# Supply_Wenzel.net
KiCad netlist of a schematic drawn in Altium Designer
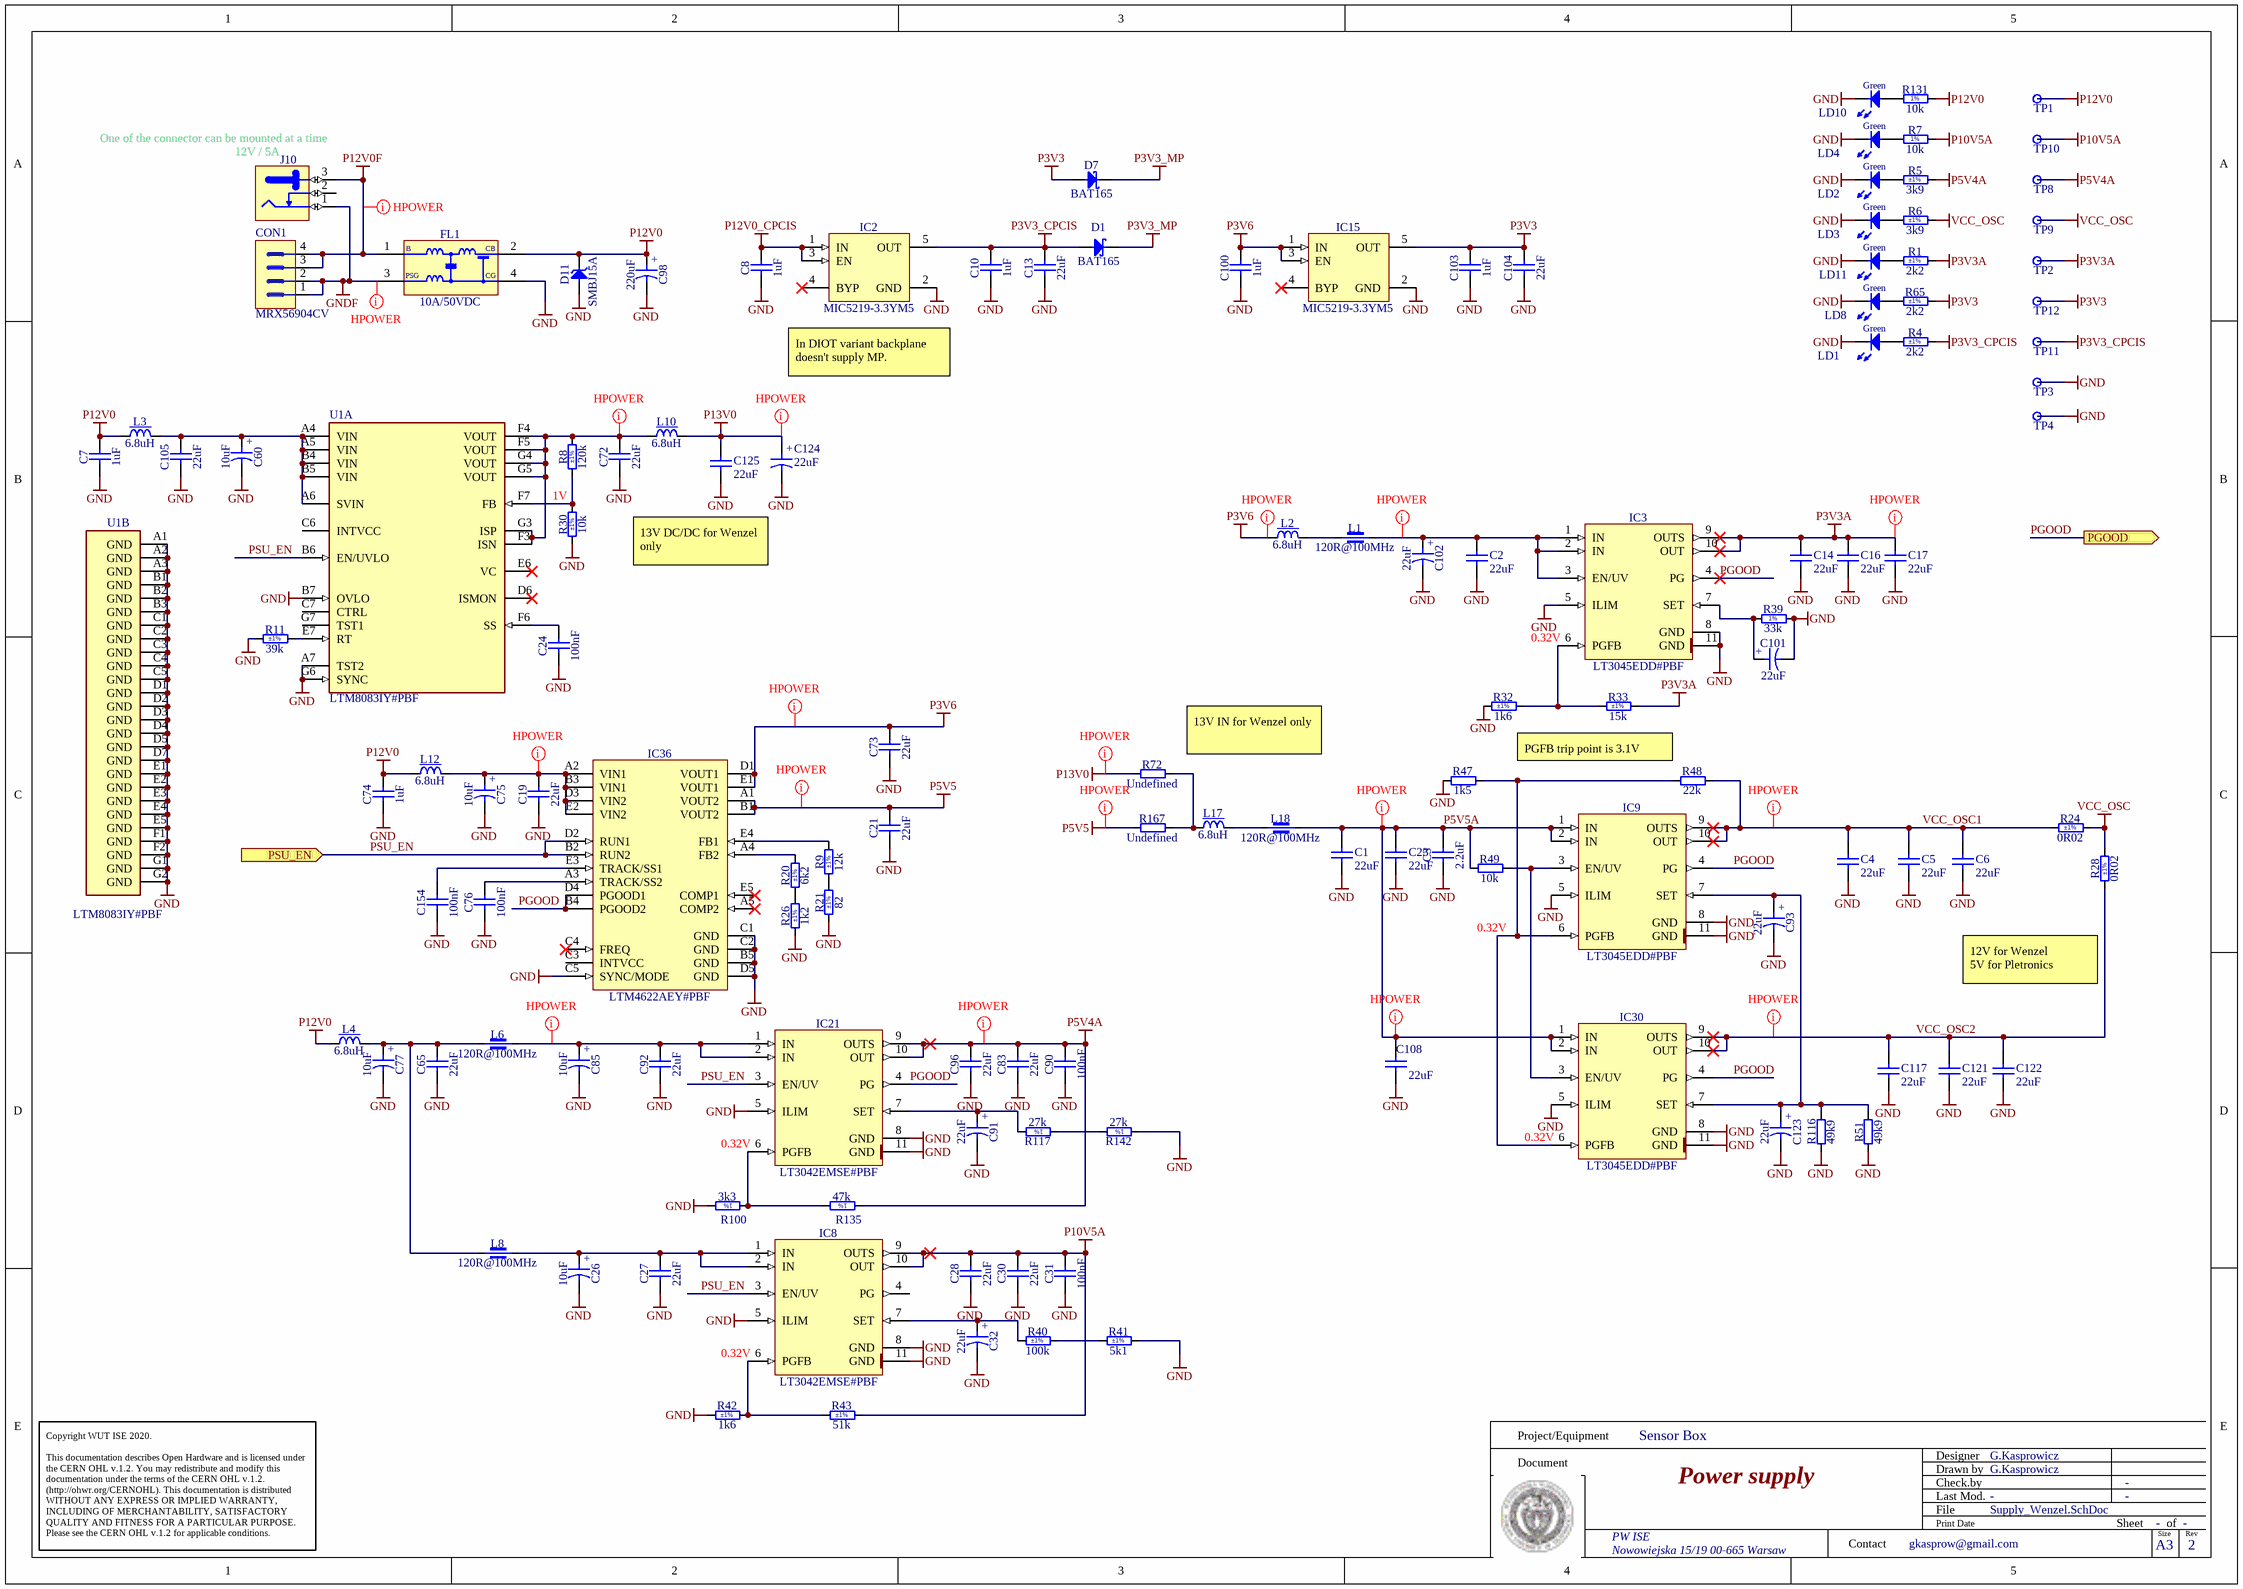
[diagram p0: Supply_Wenzel.SchDoc]

(export (version "E")
  (design (tool "Eeschema 10.0.6"))
  (components
    (comp (ref "C1")
      (value "22uF")
      (footprint "CAPC2012X135N")
      (description "Non-polarised capacitor")
      (fields
        (field (name "PART NUMBER") "CC0805_22UF_16V_10%_X5R")
        (field (name "VOLTAGE") "16V")
        (field (name "AUTHOR") "CERN DEM JLC")
      )
      (libsource (lib "Capacitors") (part "Capacitor - non polarized"))
    )
    (comp (ref "C2")
      (value "22uF")
      (footprint "CAPC2012X135N")
      (description "Non-polarised capacitor")
      (fields
        (field (name "PART NUMBER") "CC0805_22UF_16V_10%_X5R")
        (field (name "VOLTAGE") "16V")
        (field (name "AUTHOR") "CERN DEM JLC")
      )
      (libsource (lib "Capacitors") (part "Capacitor - non polarized"))
    )
    (comp (ref "C3")
      (value "2.2uF")
      (footprint "CAPC1608X87N")
      (description "Non-polarised capacitor")
      (fields
        (field (name "PART NUMBER") "CC0603_2.2UF_16V_10%_X5R")
        (field (name "VOLTAGE") "16V")
        (field (name "AUTHOR") "CERN DEM JLC")
      )
      (libsource (lib "Capacitors") (part "Capacitor - non polarized"))
    )
    (comp (ref "C4")
      (value "22uF")
      (footprint "CAPC2012X135N")
      (description "Non-polarised capacitor")
      (fields
        (field (name "PART NUMBER") "CC0805_22UF_16V_10%_X5R")
        (field (name "VOLTAGE") "16V")
        (field (name "AUTHOR") "CERN DEM JLC")
      )
      (libsource (lib "Capacitors") (part "Capacitor - non polarized"))
    )
    (comp (ref "C5")
      (value "22uF")
      (footprint "CAPC2012X135N")
      (description "Non-polarised capacitor")
      (fields
        (field (name "PART NUMBER") "CC0805_22UF_16V_10%_X5R")
        (field (name "VOLTAGE") "16V")
        (field (name "AUTHOR") "CERN DEM JLC")
      )
      (libsource (lib "Capacitors") (part "Capacitor - non polarized"))
    )
    (comp (ref "C6")
      (value "22uF")
      (footprint "CAPC2012X135N")
      (description "Non-polarised capacitor")
      (fields
        (field (name "PART NUMBER") "CC0805_22UF_16V_10%_X5R")
        (field (name "VOLTAGE") "16V")
        (field (name "AUTHOR") "CERN DEM JLC")
      )
      (libsource (lib "Capacitors") (part "Capacitor - non polarized"))
    )
    (comp (ref "C7")
      (value "1uF")
      (footprint "CAPC1608X87N")
      (description "Non-polarised capacitor")
      (fields
        (field (name "PART NUMBER") "CC0603_1UF_25V_10%_X7R")
        (field (name "VOLTAGE") "25V")
        (field (name "AUTHOR") "CERN DEM JLC")
      )
      (libsource (lib "Capacitors") (part "Capacitor - non polarized"))
    )
    (comp (ref "C8")
      (value "1uF")
      (footprint "CAPC1608X87N")
      (description "Non-polarised capacitor")
      (fields
        (field (name "PART NUMBER") "CC0603_1UF_25V_10%_X7R")
        (field (name "VOLTAGE") "25V")
        (field (name "AUTHOR") "CERN DEM JLC")
      )
      (libsource (lib "Capacitors") (part "Capacitor - non polarized"))
    )
    (comp (ref "C10")
      (value "1uF")
      (footprint "CAPC1608X87N")
      (description "Non-polarised capacitor")
      (fields
        (field (name "PART NUMBER") "CC0603_1UF_25V_10%_X7R")
        (field (name "VOLTAGE") "25V")
        (field (name "AUTHOR") "CERN DEM JLC")
      )
      (libsource (lib "Capacitors") (part "Capacitor - non polarized"))
    )
    (comp (ref "C13")
      (value "22uF")
      (footprint "CAPC1608X90N")
      (description "Non-polarised capacitor")
      (fields
        (field (name "PART NUMBER") "CC0603_22UF_6.3V_20%_X5R")
        (field (name "VOLTAGE") "6.3V")
        (field (name "AUTHOR") "CERN DEM JLC")
      )
      (libsource (lib "Capacitors") (part "Capacitor - non polarized"))
    )
    (comp (ref "C14")
      (value "22uF")
      (footprint "CAPC2012X135N")
      (description "Non-polarised capacitor")
      (fields
        (field (name "PART NUMBER") "CC0805_22UF_16V_10%_X5R")
        (field (name "VOLTAGE") "16V")
        (field (name "AUTHOR") "CERN DEM JLC")
      )
      (libsource (lib "Capacitors") (part "Capacitor - non polarized"))
    )
    (comp (ref "C16")
      (value "22uF")
      (footprint "CAPC2012X135N")
      (description "Non-polarised capacitor")
      (fields
        (field (name "PART NUMBER") "CC0805_22UF_16V_10%_X5R")
        (field (name "VOLTAGE") "16V")
        (field (name "AUTHOR") "CERN DEM JLC")
      )
      (libsource (lib "Capacitors") (part "Capacitor - non polarized"))
    )
    (comp (ref "C17")
      (value "22uF")
      (footprint "CAPC2012X135N")
      (description "Non-polarised capacitor")
      (fields
        (field (name "PART NUMBER") "CC0805_22UF_16V_10%_X5R")
        (field (name "VOLTAGE") "16V")
        (field (name "AUTHOR") "CERN DEM JLC")
      )
      (libsource (lib "Capacitors") (part "Capacitor - non polarized"))
    )
    (comp (ref "C19")
      (value "22uF")
      (footprint "CAPC2012X135N")
      (description "Non-polarised capacitor")
      (fields
        (field (name "PART NUMBER") "CC0805_22UF_16V_10%_X5R")
        (field (name "VOLTAGE") "16V")
        (field (name "AUTHOR") "CERN DEM JLC")
      )
      (libsource (lib "Capacitors") (part "Capacitor - non polarized"))
    )
    (comp (ref "C21")
      (value "22uF")
      (footprint "CAPC2012X135N")
      (description "Non-polarised capacitor")
      (fields
        (field (name "PART NUMBER") "CC0805_22UF_16V_10%_X5R")
        (field (name "VOLTAGE") "16V")
        (field (name "AUTHOR") "CERN DEM JLC")
      )
      (libsource (lib "Capacitors") (part "Capacitor - non polarized"))
    )
    (comp (ref "C23")
      (value "22uF")
      (footprint "CAPC2012X135N")
      (description "Non-polarised capacitor")
      (fields
        (field (name "PART NUMBER") "CC0805_22UF_16V_10%_X5R")
        (field (name "VOLTAGE") "16V")
        (field (name "AUTHOR") "CERN DEM JLC")
      )
      (libsource (lib "Capacitors") (part "Capacitor - non polarized"))
    )
    (comp (ref "C24")
      (value "100nF")
      (footprint "CAPC1005X55N")
      (description "Non-polarised capacitor")
      (fields
        (field (name "PART NUMBER") "CC0402_100NF_16V_10%_X7R")
        (field (name "VOLTAGE") "16V")
        (field (name "AUTHOR") "CERN DEM JLC")
      )
      (libsource (lib "Capacitors") (part "Capacitor - non polarized"))
    )
    (comp (ref "C26")
      (value "10uF")
      (footprint "CAPMP3216X180N")
      (description "Polarised capacitor")
      (fields
        (field (name "PART NUMBER") "CTE3216-18_10UF_16V_20%_AVX_TCJ")
        (field (name "VOLTAGE") "16V")
        (field (name "AUTHOR") "CERN DEM JLC")
      )
      (libsource (lib "Capacitors") (part "Capacitor - polarized"))
    )
    (comp (ref "C27")
      (value "22uF")
      (footprint "CAPC2012X135N")
      (description "Non-polarised capacitor")
      (fields
        (field (name "PART NUMBER") "CC0805_22UF_16V_10%_X5R")
        (field (name "VOLTAGE") "16V")
        (field (name "AUTHOR") "CERN DEM JLC")
      )
      (libsource (lib "Capacitors") (part "Capacitor - non polarized"))
    )
    (comp (ref "C28")
      (value "22uF")
      (footprint "CAPC2012X135N")
      (description "Non-polarised capacitor")
      (fields
        (field (name "PART NUMBER") "CC0805_22UF_16V_10%_X5R")
        (field (name "VOLTAGE") "16V")
        (field (name "AUTHOR") "CERN DEM JLC")
      )
      (libsource (lib "Capacitors") (part "Capacitor - non polarized"))
    )
    (comp (ref "C30")
      (value "22uF")
      (footprint "CAPC2012X135N")
      (description "Non-polarised capacitor")
      (fields
        (field (name "PART NUMBER") "CC0805_22UF_16V_10%_X5R")
        (field (name "VOLTAGE") "16V")
        (field (name "AUTHOR") "CERN DEM JLC")
      )
      (libsource (lib "Capacitors") (part "Capacitor - non polarized"))
    )
    (comp (ref "C31")
      (value "100nF")
      (footprint "CAPC1005X55N")
      (description "Non-polarised capacitor")
      (fields
        (field (name "PART NUMBER") "CC0402_100NF_16V_10%_X5R")
        (field (name "VOLTAGE") "16V")
        (field (name "AUTHOR") "CERN DEM JLC")
      )
      (libsource (lib "Capacitors") (part "Capacitor - non polarized"))
    )
    (comp (ref "C32")
      (value "22uF")
      (footprint "CAPMP3528X210N")
      (description "Polarised capacitor")
      (fields
        (field (name "PART NUMBER") "CTE3528-21_22UF_10V_10%_LESR0700")
        (field (name "VOLTAGE") "10V")
        (field (name "AUTHOR") "CERN DEM JLC")
      )
      (libsource (lib "Capacitors") (part "Capacitor - polarized"))
    )
    (comp (ref "C60")
      (value "10uF")
      (footprint "CAPMP3216X180N")
      (description "Polarised capacitor")
      (fields
        (field (name "PART NUMBER") "CTE3216-18_10UF_16V_20%_AVX_TCJ")
        (field (name "VOLTAGE") "16V")
        (field (name "AUTHOR") "CERN DEM JLC")
      )
      (libsource (lib "Capacitors") (part "Capacitor - polarized"))
    )
    (comp (ref "C65")
      (value "22uF")
      (footprint "CAPC2012X135N")
      (description "Non-polarised capacitor")
      (fields
        (field (name "PART NUMBER") "CC0805_22UF_16V_10%_X5R")
        (field (name "VOLTAGE") "16V")
        (field (name "AUTHOR") "CERN DEM JLC")
      )
      (libsource (lib "Capacitors") (part "Capacitor - non polarized"))
    )
    (comp (ref "C72")
      (value "22uF")
      (footprint "CAPC2012X135N")
      (description "Non-polarised capacitor")
      (fields
        (field (name "PART NUMBER") "CC0805_22UF_16V_10%_X5R")
        (field (name "VOLTAGE") "16V")
        (field (name "AUTHOR") "CERN DEM JLC")
      )
      (libsource (lib "Capacitors") (part "Capacitor - non polarized"))
    )
    (comp (ref "C73")
      (value "22uF")
      (footprint "CAPC2012X135N")
      (description "Non-polarised capacitor")
      (fields
        (field (name "PART NUMBER") "CC0805_22UF_16V_10%_X5R")
        (field (name "VOLTAGE") "16V")
        (field (name "AUTHOR") "CERN DEM JLC")
      )
      (libsource (lib "Capacitors") (part "Capacitor - non polarized"))
    )
    (comp (ref "C74")
      (value "1uF")
      (footprint "CAPC1608X87N")
      (description "Non-polarised capacitor")
      (fields
        (field (name "PART NUMBER") "CC0603_1UF_25V_10%_X7R")
        (field (name "VOLTAGE") "25V")
        (field (name "AUTHOR") "CERN DEM JLC")
      )
      (libsource (lib "Capacitors") (part "Capacitor - non polarized"))
    )
    (comp (ref "C75")
      (value "10uF")
      (footprint "CAPMP3216X180N")
      (description "Polarised capacitor")
      (fields
        (field (name "PART NUMBER") "CTE3216-18_10UF_16V_20%_AVX_TCJ")
        (field (name "VOLTAGE") "16V")
        (field (name "AUTHOR") "CERN DEM JLC")
      )
      (libsource (lib "Capacitors") (part "Capacitor - polarized"))
    )
    (comp (ref "C76")
      (value "100nF")
      (footprint "CAPC1005X55N")
      (description "Non-polarised capacitor")
      (fields
        (field (name "PART NUMBER") "CC0402_100NF_16V_10%_X7R")
        (field (name "VOLTAGE") "16V")
        (field (name "AUTHOR") "CERN DEM JLC")
      )
      (libsource (lib "Capacitors") (part "Capacitor - non polarized"))
    )
    (comp (ref "C77")
      (value "10uF")
      (footprint "CAPMP3216X180N")
      (description "Polarised capacitor")
      (fields
        (field (name "PART NUMBER") "CTE3216-18_10UF_16V_20%_AVX_TCJ")
        (field (name "VOLTAGE") "16V")
        (field (name "AUTHOR") "CERN DEM JLC")
      )
      (libsource (lib "Capacitors") (part "Capacitor - polarized"))
    )
    (comp (ref "C83")
      (value "22uF")
      (footprint "CAPC2012X135N")
      (description "Non-polarised capacitor")
      (fields
        (field (name "PART NUMBER") "CC0805_22UF_16V_10%_X5R")
        (field (name "VOLTAGE") "16V")
        (field (name "AUTHOR") "CERN DEM JLC")
      )
      (libsource (lib "Capacitors") (part "Capacitor - non polarized"))
    )
    (comp (ref "C85")
      (value "10uF")
      (footprint "CAPMP3216X180N")
      (description "Polarised capacitor")
      (fields
        (field (name "PART NUMBER") "CTE3216-18_10UF_16V_20%_AVX_TCJ")
        (field (name "VOLTAGE") "16V")
        (field (name "AUTHOR") "CERN DEM JLC")
      )
      (libsource (lib "Capacitors") (part "Capacitor - polarized"))
    )
    (comp (ref "C90")
      (value "100nF")
      (footprint "CAPC1005X55N")
      (description "Non-polarised capacitor")
      (fields
        (field (name "PART NUMBER") "CC0402_100NF_16V_10%_X5R")
        (field (name "VOLTAGE") "16V")
        (field (name "AUTHOR") "CERN DEM JLC")
      )
      (libsource (lib "Capacitors") (part "Capacitor - non polarized"))
    )
    (comp (ref "C91")
      (value "22uF")
      (footprint "CAPMP3528X210N")
      (description "Polarised capacitor")
      (fields
        (field (name "PART NUMBER") "CTE3528-21_22UF_10V_10%_LESR0700")
        (field (name "VOLTAGE") "10V")
        (field (name "AUTHOR") "CERN DEM JLC")
      )
      (libsource (lib "Capacitors") (part "Capacitor - polarized"))
    )
    (comp (ref "C92")
      (value "22uF")
      (footprint "CAPC2012X135N")
      (description "Non-polarised capacitor")
      (fields
        (field (name "PART NUMBER") "CC0805_22UF_16V_10%_X5R")
        (field (name "VOLTAGE") "16V")
        (field (name "AUTHOR") "CERN DEM JLC")
      )
      (libsource (lib "Capacitors") (part "Capacitor - non polarized"))
    )
    (comp (ref "C93")
      (value "22uF")
      (footprint "CAPMP3528X210N")
      (description "Polarised capacitor")
      (fields
        (field (name "PART NUMBER") "CTE3528-21_22UF_20V_10%_LESR0400")
        (field (name "VOLTAGE") "20V")
        (field (name "AUTHOR") "CERN DEM JLC")
      )
      (libsource (lib "Capacitors") (part "Capacitor - polarized"))
    )
    (comp (ref "C96")
      (value "22uF")
      (footprint "CAPC2012X135N")
      (description "Non-polarised capacitor")
      (fields
        (field (name "PART NUMBER") "CC0805_22UF_16V_10%_X5R")
        (field (name "VOLTAGE") "16V")
        (field (name "AUTHOR") "CERN DEM JLC")
      )
      (libsource (lib "Capacitors") (part "Capacitor - non polarized"))
    )
    (comp (ref "C98")
      (value "220uF")
      (footprint "CAPAE830X620N")
      (description "Polarised capacitor")
      (fields
        (field (name "PART NUMBER") "CAE830-620_220UF_16V_20%")
        (field (name "VOLTAGE") "16V")
        (field (name "AUTHOR") "CERN DEM JLC")
      )
      (libsource (lib "Capacitors") (part "Capacitor - polarized"))
    )
    (comp (ref "C100")
      (value "1uF")
      (footprint "CAPC1608X87N")
      (description "Non-polarised capacitor")
      (fields
        (field (name "PART NUMBER") "CC0603_1UF_25V_10%_X7R")
        (field (name "VOLTAGE") "25V")
        (field (name "AUTHOR") "CERN DEM JLC")
      )
      (libsource (lib "Capacitors") (part "Capacitor - non polarized"))
    )
    (comp (ref "C101")
      (value "22uF")
      (footprint "CAPMP3216X180N")
      (description "Polarised capacitor")
      (fields
        (field (name "PART NUMBER") "CTE3216-18_22UF_6.3V_10%_LESR0900")
        (field (name "VOLTAGE") "6.3V")
        (field (name "AUTHOR") "CERN DEM JLC")
      )
      (libsource (lib "Capacitors") (part "Capacitor - polarized"))
    )
    (comp (ref "C102")
      (value "22uF")
      (footprint "CAPMP3216X180N")
      (description "Polarised capacitor")
      (fields
        (field (name "PART NUMBER") "CTE3216-18_22UF_6.3V_10%_LESR0900")
        (field (name "VOLTAGE") "6.3V")
        (field (name "AUTHOR") "CERN DEM JLC")
      )
      (libsource (lib "Capacitors") (part "Capacitor - polarized"))
    )
    (comp (ref "C103")
      (value "1uF")
      (footprint "CAPC1608X87N")
      (description "Non-polarised capacitor")
      (fields
        (field (name "PART NUMBER") "CC0603_1UF_25V_10%_X7R")
        (field (name "VOLTAGE") "25V")
        (field (name "AUTHOR") "CERN DEM JLC")
      )
      (libsource (lib "Capacitors") (part "Capacitor - non polarized"))
    )
    (comp (ref "C104")
      (value "22uF")
      (footprint "CAPC1608X90N")
      (description "Non-polarised capacitor")
      (fields
        (field (name "PART NUMBER") "CC0603_22UF_6.3V_20%_X5R")
        (field (name "VOLTAGE") "6.3V")
        (field (name "AUTHOR") "CERN DEM JLC")
      )
      (libsource (lib "Capacitors") (part "Capacitor - non polarized"))
    )
    (comp (ref "C105")
      (value "22uF")
      (footprint "CAPC2012X135N")
      (description "Non-polarised capacitor")
      (fields
        (field (name "PART NUMBER") "CC0805_22UF_16V_10%_X5R")
        (field (name "VOLTAGE") "16V")
        (field (name "AUTHOR") "CERN DEM JLC")
      )
      (libsource (lib "Capacitors") (part "Capacitor - non polarized"))
    )
    (comp (ref "C108")
      (value "22uF")
      (footprint "CAPC2012X135N")
      (description "Non-polarised capacitor")
      (fields
        (field (name "PART NUMBER") "CC0805_22UF_16V_10%_X5R")
        (field (name "VOLTAGE") "16V")
        (field (name "AUTHOR") "CERN DEM JLC")
      )
      (libsource (lib "Capacitors") (part "Capacitor - non polarized"))
    )
    (comp (ref "C117")
      (value "22uF")
      (footprint "CAPC2012X135N")
      (description "Non-polarised capacitor")
      (fields
        (field (name "PART NUMBER") "CC0805_22UF_16V_10%_X5R")
        (field (name "VOLTAGE") "16V")
        (field (name "AUTHOR") "CERN DEM JLC")
      )
      (libsource (lib "Capacitors") (part "Capacitor - non polarized"))
    )
    (comp (ref "C121")
      (value "22uF")
      (footprint "CAPC2012X135N")
      (description "Non-polarised capacitor")
      (fields
        (field (name "PART NUMBER") "CC0805_22UF_16V_10%_X5R")
        (field (name "VOLTAGE") "16V")
        (field (name "AUTHOR") "CERN DEM JLC")
      )
      (libsource (lib "Capacitors") (part "Capacitor - non polarized"))
    )
    (comp (ref "C122")
      (value "22uF")
      (footprint "CAPC2012X135N")
      (description "Non-polarised capacitor")
      (fields
        (field (name "PART NUMBER") "CC0805_22UF_16V_10%_X5R")
        (field (name "VOLTAGE") "16V")
        (field (name "AUTHOR") "CERN DEM JLC")
      )
      (libsource (lib "Capacitors") (part "Capacitor - non polarized"))
    )
    (comp (ref "C123")
      (value "22uF")
      (footprint "CAPMP3528X210N")
      (description "Polarised capacitor")
      (fields
        (field (name "PART NUMBER") "CTE3528-21_22UF_20V_10%_LESR0400")
        (field (name "VOLTAGE") "20V")
        (field (name "AUTHOR") "CERN DEM JLC")
      )
      (libsource (lib "Capacitors") (part "Capacitor - polarized"))
    )
    (comp (ref "C124")
      (value "22uF")
      (footprint "CAPMP3528X210N")
      (description "Polarised capacitor")
      (fields
        (field (name "PART NUMBER") "CTE3528-21_22UF_20V_10%_LESR0400")
        (field (name "VOLTAGE") "20V")
        (field (name "AUTHOR") "CERN DEM JLC")
      )
      (libsource (lib "Capacitors") (part "Capacitor - polarized"))
    )
    (comp (ref "C125")
      (value "22uF")
      (footprint "CAPC2012X135N")
      (description "Non-polarised capacitor")
      (fields
        (field (name "PART NUMBER") "CC0805_22UF_16V_10%_X5R")
        (field (name "VOLTAGE") "16V")
        (field (name "AUTHOR") "CERN DEM JLC")
      )
      (libsource (lib "Capacitors") (part "Capacitor - non polarized"))
    )
    (comp (ref "C154")
      (value "100nF")
      (footprint "CAPC1005X55N")
      (description "Non-polarised capacitor")
      (fields
        (field (name "PART NUMBER") "CC0402_100NF_16V_10%_X7R")
        (field (name "VOLTAGE") "16V")
        (field (name "AUTHOR") "CERN DEM JLC")
      )
      (libsource (lib "Capacitors") (part "Capacitor - non polarized"))
    )
    (comp (ref "CON1")
      (value "MRX56904CV")
      (footprint "MRX56904CV")
      (description "4.2mm cripm terminal header")
      (libsource (lib "LIBRARY_SCH") (part "CON_CRIMP_4.2mm_RA_4"))
    )
    (comp (ref "D1")
      (value "BAT165")
      (footprint "SOD2512X110N")
      (description "Schottky Diode")
      (fields
        (field (name "MANUFACTURER") "INFINEON")
        (field (name "VOLTAGE") "40V")
        (field (name "AUTHOR") "CERN DEM JLC")
      )
      (libsource (lib "ICs And Semiconductors") (part "Diode Schottky"))
    )
    (comp (ref "D7")
      (value "BAT165")
      (footprint "SOD2512X110N")
      (description "Schottky Diode")
      (fields
        (field (name "VOLTAGE") "40V")
        (field (name "POWER") "750mA")
        (field (name "AUTHOR") "CERN DEM JLC")
      )
      (libsource (lib "ICs And Semiconductors") (part "Diode Schottky"))
    )
    (comp (ref "D11")
      (value "SMBJ15A")
      (footprint "DIOM5336X265N")
      (description "Zener Diode")
      (fields
        (field (name "VOLTAGE") "15V")
        (field (name "POWER") "600W")
        (field (name "AUTHOR") "CERN DEM JLC")
      )
      (libsource (lib "ICs And Semiconductors") (part "Diode Zener"))
    )
    (comp (ref "FL1")
      (value "10A/50VDC")
      (footprint "FIL_MURATA_BNX02")
      (description "Block Type EMIFIL (LC Combined)")
      (fields
        (field (name "PART NUMBER") "FIL_MURATA_BNX022-01L")
        (field (name "MANUFACTURER") "MURATA")
        (field (name "AUTHOR") "CERN DEM JLC")
      )
      (libsource (lib "Inductors & Transformers") (part "FIL_MURATA_BNX02"))
    )
    (comp (ref "IC2")
      (value "MIC5219-3.3YM5")
      (footprint "SOT95P280X145-5N")
      (description "500mA Peak Output LDO Regulator")
      (fields (field (name "MANUFACTURER") "MICROCHIP TECHNOLOGY") (field (name "AUTHOR") "CERN DEM WB"))
      (libsource (lib "ICs And Semiconductors") (part "MIC5219-X.XYM5"))
    )
    (comp (ref "IC3")
      (value "LT3045EDD#PBF")
      (footprint "SON50P300X300X80-11N-R175X248")
      (description "20V, 500mA, Ultralow Noise, Ultrahigh PSRR Linear Regulator")
      (fields (field (name "MANUFACTURER") "LINEAR TECHNOLOGY") (field (name "AUTHOR") "CERN DEM JLC"))
      (libsource (lib "ICs And Semiconductors") (part "LT3045EDD"))
    )
    (comp (ref "IC8")
      (value "LT3042EMSE#PBF")
      (footprint "SOP50P490X110-11N-R168X198")
      (description "20V, 200mA, Ultralow Noise, Ultrahigh PSRR RF Linear Regulator")
      (fields (field (name "MANUFACTURER") "LINEAR TECHNOLOGY") (field (name "AUTHOR") "CERN DEM MR"))
      (libsource (lib "ICs And Semiconductors") (part "LT3042"))
    )
    (comp (ref "IC9")
      (value "LT3045EDD#PBF")
      (footprint "SON50P300X300X80-11N-R175X248")
      (description "20V, 500mA, Ultralow Noise, Ultrahigh PSRR Linear Regulator")
      (fields (field (name "MANUFACTURER") "LINEAR TECHNOLOGY") (field (name "AUTHOR") "CERN DEM JLC"))
      (libsource (lib "ICs And Semiconductors") (part "LT3045EDD"))
    )
    (comp (ref "IC15")
      (value "MIC5219-3.3YM5")
      (footprint "SOT95P280X145-5N")
      (description "500mA Peak Output LDO Regulator")
      (fields (field (name "MANUFACTURER") "MICROCHIP TECHNOLOGY") (field (name "AUTHOR") "CERN DEM WB"))
      (libsource (lib "ICs And Semiconductors") (part "MIC5219-X.XYM5"))
    )
    (comp (ref "IC21")
      (value "LT3042EMSE#PBF")
      (footprint "SOP50P490X110-11N-R168X198")
      (description "20V, 200mA, Ultralow Noise, Ultrahigh PSRR RF Linear Regulator")
      (fields (field (name "MANUFACTURER") "LINEAR TECHNOLOGY") (field (name "AUTHOR") "CERN DEM MR"))
      (libsource (lib "ICs And Semiconductors") (part "LT3042"))
    )
    (comp (ref "IC30")
      (value "LT3045EDD#PBF")
      (footprint "SON50P300X300X80-11N-R175X248")
      (description "20V, 500mA, Ultralow Noise, Ultrahigh PSRR Linear Regulator")
      (fields (field (name "MANUFACTURER") "LINEAR TECHNOLOGY") (field (name "AUTHOR") "CERN DEM JLC"))
      (libsource (lib "ICs And Semiconductors") (part "LT3045EDD"))
    )
    (comp (ref "IC36")
      (value "LTM4622AEY#PBF")
      (footprint "BGA25C127P5X5_625X625X262")
      (description "3.6V-20V To 1.5V-12V, Dual 2A or Single 4A  Ultrathin Step-Down DC/DC µModule Regulator")
      (fields (field (name "MANUFACTURER") "LINEAR TECHNOLOGY") (field (name "AUTHOR") "CERN DEM MR"))
      (libsource (lib "ICs And Semiconductors") (part "LTM4622A"))
    )
    (comp (ref "J10")
      (value "Jack")
      (footprint "SWITCHCRAFT_L712RA")
      (description "24V /3. 5A, 2.1mm Diameter Pin, SMD DC Power Supply Connector With  Break Contact")
      (fields
        (field (name "PART NUMBER") "SWITCHCRAFT_L712RA")
        (field (name "MANUFACTURER") "SWITCHCRAFT")
        (field (name "AUTHOR") "GK")
      )
      (libsource (lib "LIBRARY_SCH") (part "CON_DC_5A_THT_RA"))
    )
    (comp (ref "L1")
      (value "120R@100MHz")
      (footprint "INDC1608X65N")
      (fields
        (field (name "PART NUMBER") "IND0603_MURATA_BLM18SG121TN1D")
        (field (name "POWER") "3A")
        (field (name "TOLERANCE") "±25%")
        (field (name "AUTHOR") "CERN DEM JLC")
      )
      (libsource (lib "Inductors & Transformers") (part "Ferrite Bead"))
    )
    (comp (ref "L2")
      (value "6.8uH")
      (footprint "IND_COILCRAFT_XAL4030")
      (description "Inductor With Core")
      (fields
        (field (name "PART NUMBER") "IND_6.8UH_20%_COILCRAFT_XAL4030")
        (field (name "POWER") "3A")
        (field (name "AUTHOR") "CERN DEM MR")
      )
      (libsource (lib "Inductors & Transformers") (part "Inductor With Magnetic core"))
    )
    (comp (ref "L3")
      (value "6.8uH")
      (footprint "IND_COILCRAFT_XAL4030")
      (description "Inductor With Core")
      (fields
        (field (name "PART NUMBER") "IND_6.8UH_20%_COILCRAFT_XAL4030")
        (field (name "POWER") "3A")
        (field (name "AUTHOR") "CERN DEM MR")
      )
      (libsource (lib "Inductors & Transformers") (part "Inductor With Magnetic core"))
    )
    (comp (ref "L4")
      (value "6.8uH")
      (footprint "IND_COILCRAFT_XAL4030")
      (description "Inductor With Core")
      (fields
        (field (name "PART NUMBER") "IND_6.8UH_20%_COILCRAFT_XAL4030")
        (field (name "POWER") "3A")
        (field (name "AUTHOR") "CERN DEM MR")
      )
      (libsource (lib "Inductors & Transformers") (part "Inductor With Magnetic core"))
    )
    (comp (ref "L6")
      (value "120R@100MHz")
      (footprint "INDC1608X65N")
      (fields
        (field (name "PART NUMBER") "IND0603_MURATA_BLM18SG121TN1D")
        (field (name "POWER") "3A")
        (field (name "TOLERANCE") "±25%")
        (field (name "AUTHOR") "CERN DEM JLC")
      )
      (libsource (lib "Inductors & Transformers") (part "Ferrite Bead"))
    )
    (comp (ref "L8")
      (value "120R@100MHz")
      (footprint "INDC1608X65N")
      (fields
        (field (name "PART NUMBER") "IND0603_MURATA_BLM18SG121TN1D")
        (field (name "POWER") "3A")
        (field (name "TOLERANCE") "±25%")
        (field (name "AUTHOR") "CERN DEM JLC")
      )
      (libsource (lib "Inductors & Transformers") (part "Ferrite Bead"))
    )
    (comp (ref "L10")
      (value "6.8uH")
      (footprint "IND_COILCRAFT_XAL4030")
      (description "Inductor With Core")
      (fields
        (field (name "PART NUMBER") "IND_6.8UH_20%_COILCRAFT_XAL4030")
        (field (name "POWER") "3A")
        (field (name "AUTHOR") "CERN DEM MR")
      )
      (libsource (lib "Inductors & Transformers") (part "Inductor With Magnetic core"))
    )
    (comp (ref "L12")
      (value "6.8uH")
      (footprint "IND_COILCRAFT_XAL4030")
      (description "Inductor With Core")
      (fields
        (field (name "PART NUMBER") "IND_6.8UH_20%_COILCRAFT_XAL4030")
        (field (name "POWER") "3A")
        (field (name "AUTHOR") "CERN DEM MR")
      )
      (libsource (lib "Inductors & Transformers") (part "Inductor With Magnetic core"))
    )
    (comp (ref "L17")
      (value "6.8uH")
      (footprint "IND_COILCRAFT_XAL4030")
      (description "Inductor With Core")
      (fields
        (field (name "PART NUMBER") "IND_6.8UH_20%_COILCRAFT_XAL4030")
        (field (name "POWER") "3A")
        (field (name "AUTHOR") "CERN DEM MR")
      )
      (libsource (lib "Inductors & Transformers") (part "Inductor With Magnetic core"))
    )
    (comp (ref "L18")
      (value "120R@100MHz")
      (footprint "INDC1608X65N")
      (fields
        (field (name "PART NUMBER") "IND0603_MURATA_BLM18SG121TN1D")
        (field (name "POWER") "3A")
        (field (name "TOLERANCE") "±25%")
        (field (name "AUTHOR") "CERN DEM JLC")
      )
      (libsource (lib "Inductors & Transformers") (part "Ferrite Bead"))
    )
    (comp (ref "LD1")
      (value "Green")
      (footprint "LED_KINGBRIGHT_KPH-1608CGCK")
      (description "LED Green 1C 2A")
      (fields
        (field (name "PART NUMBER") "LED_KINGBRIGHT_KPH-1608CGCK")
        (field (name "MANUFACTURER") "KINGBRIGHT")
        (field (name "AUTHOR") "CERN DEM JLC")
      )
      (libsource (lib "ICs And Semiconductors") (part "LED Green 1C 2A"))
    )
    (comp (ref "LD2")
      (value "Green")
      (footprint "LED_KINGBRIGHT_KPH-1608CGCK")
      (description "LED Green 1C 2A")
      (fields
        (field (name "PART NUMBER") "LED_KINGBRIGHT_KPH-1608CGCK")
        (field (name "MANUFACTURER") "KINGBRIGHT")
        (field (name "AUTHOR") "CERN DEM JLC")
      )
      (libsource (lib "ICs And Semiconductors") (part "LED Green 1C 2A"))
    )
    (comp (ref "LD3")
      (value "Green")
      (footprint "LED_KINGBRIGHT_KPH-1608CGCK")
      (description "LED Green 1C 2A")
      (fields
        (field (name "PART NUMBER") "LED_KINGBRIGHT_KPH-1608CGCK")
        (field (name "MANUFACTURER") "KINGBRIGHT")
        (field (name "AUTHOR") "CERN DEM JLC")
      )
      (libsource (lib "ICs And Semiconductors") (part "LED Green 1C 2A"))
    )
    (comp (ref "LD4")
      (value "Green")
      (footprint "LED_KINGBRIGHT_KPH-1608CGCK")
      (description "LED Green 1C 2A")
      (fields
        (field (name "PART NUMBER") "LED_KINGBRIGHT_KPH-1608CGCK")
        (field (name "MANUFACTURER") "KINGBRIGHT")
        (field (name "AUTHOR") "CERN DEM JLC")
      )
      (libsource (lib "ICs And Semiconductors") (part "LED Green 1C 2A"))
    )
    (comp (ref "LD8")
      (value "Green")
      (footprint "LED_KINGBRIGHT_KPH-1608CGCK")
      (description "LED Green 1C 2A")
      (fields
        (field (name "PART NUMBER") "LED_KINGBRIGHT_KPH-1608CGCK")
        (field (name "MANUFACTURER") "KINGBRIGHT")
        (field (name "AUTHOR") "CERN DEM JLC")
      )
      (libsource (lib "ICs And Semiconductors") (part "LED Green 1C 2A"))
    )
    (comp (ref "LD10")
      (value "Green")
      (footprint "LED_KINGBRIGHT_KPH-1608CGCK")
      (description "LED Green 1C 2A")
      (fields
        (field (name "PART NUMBER") "LED_KINGBRIGHT_KPH-1608CGCK")
        (field (name "MANUFACTURER") "KINGBRIGHT")
        (field (name "AUTHOR") "CERN DEM JLC")
      )
      (libsource (lib "ICs And Semiconductors") (part "LED Green 1C 2A"))
    )
    (comp (ref "LD11")
      (value "Green")
      (footprint "LED_KINGBRIGHT_KPH-1608CGCK")
      (description "LED Green 1C 2A")
      (fields
        (field (name "PART NUMBER") "LED_KINGBRIGHT_KPH-1608CGCK")
        (field (name "MANUFACTURER") "KINGBRIGHT")
        (field (name "AUTHOR") "CERN DEM JLC")
      )
      (libsource (lib "ICs And Semiconductors") (part "LED Green 1C 2A"))
    )
    (comp (ref "R1")
      (value "2k2")
      (footprint "RESC1005X40N")
      (description "Resistor - 1%")
      (fields
        (field (name "TOLERANCE") "±1%")
        (field (name "PART NUMBER") "R0402_2K2_1%_0.0625W_100PPM")
        (field (name "POWER") "0.0625W")
        (field (name "AUTHOR") "CERN DEM JLC")
      )
      (libsource (lib "Resistors") (part "Resistor - 1%"))
    )
    (comp (ref "R4")
      (value "2k2")
      (footprint "RESC1005X40N")
      (description "Resistor - 1%")
      (fields
        (field (name "TOLERANCE") "±1%")
        (field (name "PART NUMBER") "R0402_2K2_1%_0.0625W_100PPM")
        (field (name "POWER") "0.0625W")
        (field (name "AUTHOR") "CERN DEM JLC")
      )
      (libsource (lib "Resistors") (part "Resistor - 1%"))
    )
    (comp (ref "R5")
      (value "3k9")
      (footprint "RESC1005X40N")
      (description "Resistor - 1%")
      (fields
        (field (name "TOLERANCE") "±1%")
        (field (name "PART NUMBER") "R0402_3K9_1%_0.0625W_100PPM")
        (field (name "POWER") "0.0625W")
        (field (name "AUTHOR") "CERN DEM JLC")
      )
      (libsource (lib "Resistors") (part "Resistor - 1%"))
    )
    (comp (ref "R6")
      (value "3k9")
      (footprint "RESC1005X40N")
      (description "Resistor - 1%")
      (fields
        (field (name "TOLERANCE") "±1%")
        (field (name "PART NUMBER") "R0402_3K9_1%_0.0625W_100PPM")
        (field (name "POWER") "0.0625W")
        (field (name "AUTHOR") "CERN DEM JLC")
      )
      (libsource (lib "Resistors") (part "Resistor - 1%"))
    )
    (comp (ref "R7")
      (value "10k")
      (footprint "RESC1005X40N")
      (description "Resistor - 1%")
      (fields
        (field (name "PART NUMBER") "R0402_10K_1%_0.0625W_100PPM")
        (field (name "POWER") "0.0625W")
        (field (name "AUTHOR") "CERN DEM JLC")
      )
      (libsource (lib "Resistors") (part "Resistor - 1%"))
    )
    (comp (ref "R8")
      (value "120k")
      (footprint "RESC1608X55N")
      (description "Resistor - 1%")
      (fields
        (field (name "TOLERANCE") "±1%")
        (field (name "PART NUMBER") "R0603_120K_1%_0.1W_100PPM")
        (field (name "POWER") "0.1W")
        (field (name "AUTHOR") "CERN DEM JLC")
      )
      (libsource (lib "Resistors") (part "Resistor - 1%"))
    )
    (comp (ref "R9")
      (value "12k")
      (footprint "RESC1608X55N")
      (description "Resistor - 1%")
      (fields
        (field (name "TOLERANCE") "±1%")
        (field (name "PART NUMBER") "R0603_12K_1%_0.1W_100PPM")
        (field (name "POWER") "0.1W")
        (field (name "AUTHOR") "CERN DEM JLC")
      )
      (libsource (lib "Resistors") (part "Resistor - 1%"))
    )
    (comp (ref "R11")
      (value "39k")
      (footprint "RESC1005X40N")
      (description "Resistor - 1%")
      (fields
        (field (name "TOLERANCE") "±1%")
        (field (name "PART NUMBER") "R0402_39K_1%_0.0625W_100PPM")
        (field (name "POWER") "0.0625W")
        (field (name "AUTHOR") "CERN DEM JLC")
      )
      (libsource (lib "Resistors") (part "Resistor - 1%"))
    )
    (comp (ref "R20")
      (value "6k2")
      (footprint "RESC1608X55N")
      (description "Resistor - 1%")
      (fields
        (field (name "TOLERANCE") "±1%")
        (field (name "PART NUMBER") "R0603_6K2_1%_0.1W_100PPM")
        (field (name "POWER") "0.1W")
        (field (name "AUTHOR") "CERN DEM JLC")
      )
      (libsource (lib "Resistors") (part "Resistor - 1%"))
    )
    (comp (ref "R21")
      (value "82")
      (footprint "RESC1005X40N")
      (description "Resistor - 1%")
      (fields
        (field (name "TOLERANCE") "±1%")
        (field (name "PART NUMBER") "R0402_82R_1%_0.0625W_100PPM")
        (field (name "POWER") "0.0625W")
        (field (name "AUTHOR") "CERN DEM JLC")
      )
      (libsource (lib "Resistors") (part "Resistor - 1%"))
    )
    (comp (ref "R24")
      (value "0R02")
      (footprint "RESC3216X80N")
      (description "Resistor - 1%")
      (fields
        (field (name "TOLERANCE") "±1%")
        (field (name "PART NUMBER") "R1206_0R02_1%_0.5W_100PPM")
        (field (name "POWER") "0.5W")
        (field (name "AUTHOR") "CERN DEM JLC")
      )
      (libsource (lib "Resistors") (part "Resistor - 1%"))
    )
    (comp (ref "R26")
      (value "1k2")
      (footprint "RESC1608X55N")
      (description "Resistor - 1%")
      (fields
        (field (name "TOLERANCE") "±1%")
        (field (name "PART NUMBER") "R0603_1K2_1%_0.1W_100PPM")
        (field (name "POWER") "0.1W")
        (field (name "AUTHOR") "CERN DEM JLC")
      )
      (libsource (lib "Resistors") (part "Resistor - 1%"))
    )
    (comp (ref "R28")
      (value "0R02")
      (footprint "RESC3216X80N")
      (description "Resistor - 1%")
      (fields
        (field (name "TOLERANCE") "±1%")
        (field (name "PART NUMBER") "R1206_0R02_1%_0.5W_100PPM")
        (field (name "POWER") "0.5W")
        (field (name "AUTHOR") "CERN DEM JLC")
      )
      (libsource (lib "Resistors") (part "Resistor - 1%"))
    )
    (comp (ref "R30")
      (value "10k")
      (footprint "RESC1005X40N")
      (description "Resistor - 1%")
      (fields
        (field (name "TOLERANCE") "±1%")
        (field (name "PART NUMBER") "R0402_10K_1%_0.0625W_100PPM")
        (field (name "POWER") "0.0625W")
        (field (name "AUTHOR") "CERN DEM JLC")
      )
      (libsource (lib "Resistors") (part "Resistor - 1%"))
    )
    (comp (ref "R32")
      (value "1k6")
      (footprint "RESC1608X55N")
      (description "Resistor - 1%")
      (fields
        (field (name "TOLERANCE") "±1%")
        (field (name "PART NUMBER") "R0603_1K6_1%_0.1W_100PPM")
        (field (name "POWER") "0.1W")
        (field (name "AUTHOR") "CERN DEM JLC")
      )
      (libsource (lib "Resistors") (part "Resistor - 1%"))
    )
    (comp (ref "R33")
      (value "15k")
      (footprint "RESC1608X55N")
      (description "Resistor - 1%")
      (fields
        (field (name "TOLERANCE") "±1%")
        (field (name "PART NUMBER") "R0603_15K_1%_0.1W_100PPM")
        (field (name "POWER") "0.1W")
        (field (name "AUTHOR") "CERN DEM JMW")
      )
      (libsource (lib "Resistors") (part "Resistor - 1%"))
    )
    (comp (ref "R39")
      (value "33k")
      (footprint "RESC1608X55N")
      (description "Resistor - 1%")
      (fields
        (field (name "PART NUMBER") "R0603_33K_1%_0.1W_100PPM")
        (field (name "POWER") "0.1W")
        (field (name "AUTHOR") "CERN DEM JLC")
      )
      (libsource (lib "") (part "Resistor - 1%_1"))
    )
    (comp (ref "R40")
      (value "100k")
      (footprint "RESC1608X55N")
      (description "Resistor - 1%")
      (fields
        (field (name "TOLERANCE") "±1%")
        (field (name "PART NUMBER") "R0603_100K_1%_0.1W_100PPM")
        (field (name "POWER") "0.1W")
        (field (name "AUTHOR") "CERN DEM JLC")
      )
      (libsource (lib "Resistors") (part "Resistor - 1%"))
    )
    (comp (ref "R41")
      (value "5k1")
      (footprint "RESC1608X55N")
      (description "Resistor - 1%")
      (fields
        (field (name "TOLERANCE") "±1%")
        (field (name "PART NUMBER") "R0603_5K1_1%_0.1W_100PPM")
        (field (name "POWER") "0.1W")
        (field (name "AUTHOR") "CERN DEM JLC")
      )
      (libsource (lib "Resistors") (part "Resistor - 1%"))
    )
    (comp (ref "R42")
      (value "1k6")
      (footprint "RESC1608X55N")
      (description "Resistor - 1%")
      (fields
        (field (name "TOLERANCE") "±1%")
        (field (name "PART NUMBER") "R0603_1K6_1%_0.1W_100PPM")
        (field (name "POWER") "0.1W")
        (field (name "AUTHOR") "CERN DEM JLC")
      )
      (libsource (lib "Resistors") (part "Resistor - 1%"))
    )
    (comp (ref "R43")
      (value "51k")
      (footprint "RESC1608X55N")
      (description "Resistor - 1%")
      (fields
        (field (name "TOLERANCE") "±1%")
        (field (name "PART NUMBER") "R0603_51K_1%_0.1W_100PPM")
        (field (name "POWER") "0.1W")
        (field (name "AUTHOR") "CERN DEM JLC")
      )
      (libsource (lib "Resistors") (part "Resistor - 1%"))
    )
    (comp (ref "R47")
      (value "1k5")
      (footprint "RESC1005X40N")
      (description "Resistor - 1%")
      (fields
        (field (name "PART NUMBER") "R0402_1K5_1%_0.0625W_100PPM")
        (field (name "POWER") "0.0625W")
        (field (name "AUTHOR") "CERN DEM JLC")
      )
      (libsource (lib "Resistors") (part "Resistor - 1%"))
    )
    (comp (ref "R48")
      (value "22k")
      (footprint "RESC1005X40N")
      (description "Resistor - 1%")
      (fields
        (field (name "PART NUMBER") "R0402_22K_1%_0.0625W_100PPM")
        (field (name "POWER") "0.0625W")
        (field (name "AUTHOR") "CERN DEM JLC")
      )
      (libsource (lib "Resistors") (part "Resistor - 1%"))
    )
    (comp (ref "R49")
      (value "10k")
      (footprint "RESC1005X40N")
      (description "Resistor - 1%")
      (fields
        (field (name "PART NUMBER") "R0402_10K_1%_0.0625W_100PPM")
        (field (name "POWER") "0.0625W")
        (field (name "AUTHOR") "CERN DEM JLC")
      )
      (libsource (lib "Resistors") (part "Resistor - 1%"))
    )
    (comp (ref "R51")
      (value "49k9")
      (footprint "RESC1608X55N")
      (description "Resistor - 0.1%")
      (fields
        (field (name "PART NUMBER") "R0603_49K9_0.1%_0.063W_10PPM")
        (field (name "POWER") "0.063W")
        (field (name "AUTHOR") "CERN DEM JLC")
      )
      (libsource (lib "Resistors") (part "Resistor - 0.1%"))
    )
    (comp (ref "R65")
      (value "2k2")
      (footprint "RESC1005X40N")
      (description "Resistor - 1%")
      (fields
        (field (name "TOLERANCE") "±1%")
        (field (name "PART NUMBER") "R0402_2K2_1%_0.0625W_100PPM")
        (field (name "POWER") "0.0625W")
        (field (name "AUTHOR") "CERN DEM JLC")
      )
      (libsource (lib "Resistors") (part "Resistor - 1%"))
    )
    (comp (ref "R72")
      (value "Undefined")
      (footprint "RESC1608X55N")
      (description "Resistor")
      (fields (field (name "PART NUMBER") "R0603_NO-VALUE") (field (name "AUTHOR") "CERN DEM JLC"))
      (libsource (lib "Resistors") (part "Resistor"))
    )
    (comp (ref "R100")
      (value "3k3")
      (footprint "RESC1608X55N")
      (description "Resistor - 1%")
      (fields
        (field (name "PART NUMBER") "R0603_3K3_1%_0.1W_100PPM")
        (field (name "POWER") "0.1W")
        (field (name "AUTHOR") "CERN DEM JLC")
      )
      (libsource (lib "") (part "Resistor - 1%_1"))
    )
    (comp (ref "R116")
      (value "49k9")
      (footprint "RESC1608X55N")
      (description "Resistor - 0.1%")
      (fields
        (field (name "PART NUMBER") "R0603_49K9_0.1%_0.063W_10PPM")
        (field (name "POWER") "0.063W")
        (field (name "AUTHOR") "CERN DEM JLC")
      )
      (libsource (lib "Resistors") (part "Resistor - 0.1%"))
    )
    (comp (ref "R117")
      (value "27k")
      (footprint "RESC1005X40N")
      (description "Resistor - 1%")
      (fields
        (field (name "PART NUMBER") "R0402_27K_1%_0.0625W_100PPM")
        (field (name "POWER") "0.0625W")
        (field (name "AUTHOR") "CERN DEM JLC")
      )
      (libsource (lib "Resistors") (part "Resistor - 1%"))
    )
    (comp (ref "R131")
      (value "10k")
      (footprint "RESC1005X40N")
      (description "Resistor - 1%")
      (fields
        (field (name "PART NUMBER") "R0402_10K_1%_0.0625W_100PPM")
        (field (name "POWER") "0.0625W")
        (field (name "AUTHOR") "CERN DEM JLC")
      )
      (libsource (lib "Resistors") (part "Resistor - 1%"))
    )
    (comp (ref "R135")
      (value "47k")
      (footprint "RESC1005X40N")
      (description "Resistor - 1%")
      (fields
        (field (name "PART NUMBER") "R0402_47K_1%_0.0625W_100PPM")
        (field (name "POWER") "0.0625W")
        (field (name "AUTHOR") "CERN DEM JLC")
      )
      (libsource (lib "Resistors") (part "Resistor - 1%"))
    )
    (comp (ref "R142")
      (value "27k")
      (footprint "RESC1005X40N")
      (description "Resistor - 1%")
      (fields
        (field (name "PART NUMBER") "R0402_27K_1%_0.0625W_100PPM")
        (field (name "POWER") "0.0625W")
        (field (name "AUTHOR") "CERN DEM JLC")
      )
      (libsource (lib "Resistors") (part "Resistor - 1%"))
    )
    (comp (ref "R167")
      (value "Undefined")
      (footprint "RESC1608X55N")
      (description "Resistor")
      (fields (field (name "PART NUMBER") "R0603_NO-VALUE") (field (name "AUTHOR") "CERN DEM JLC"))
      (libsource (lib "Resistors") (part "Resistor"))
    )
    (comp (ref "TP1")
      (value "Test Point")
      (footprint "TPS127")
      (fields (field (name "PART NUMBER") "SMD_PAD_1.27X1.27MM") (field (name "AUTHOR") "CERN DEM JLC"))
      (libsource (lib "Eletro-mechanical") (part "Test Point"))
    )
    (comp (ref "TP2")
      (value "Test Point")
      (footprint "TPS127")
      (fields (field (name "PART NUMBER") "SMD_PAD_1.27X1.27MM") (field (name "AUTHOR") "CERN DEM JLC"))
      (libsource (lib "Eletro-mechanical") (part "Test Point"))
    )
    (comp (ref "TP3")
      (value "Test Point")
      (footprint "TPS127")
      (fields (field (name "PART NUMBER") "SMD_PAD_1.27X1.27MM") (field (name "AUTHOR") "CERN DEM JLC"))
      (libsource (lib "Eletro-mechanical") (part "Test Point"))
    )
    (comp (ref "TP4")
      (value "Test Point")
      (footprint "TPS127")
      (fields (field (name "PART NUMBER") "SMD_PAD_1.27X1.27MM") (field (name "AUTHOR") "CERN DEM JLC"))
      (libsource (lib "Eletro-mechanical") (part "Test Point"))
    )
    (comp (ref "TP8")
      (value "Test Point")
      (footprint "TPS127")
      (fields (field (name "PART NUMBER") "SMD_PAD_1.27X1.27MM") (field (name "AUTHOR") "CERN DEM JLC"))
      (libsource (lib "Eletro-mechanical") (part "Test Point"))
    )
    (comp (ref "TP9")
      (value "Test Point")
      (footprint "TPS127")
      (fields (field (name "PART NUMBER") "SMD_PAD_1.27X1.27MM") (field (name "AUTHOR") "CERN DEM JLC"))
      (libsource (lib "Eletro-mechanical") (part "Test Point"))
    )
    (comp (ref "TP10")
      (value "Test Point")
      (footprint "TPS127")
      (fields (field (name "PART NUMBER") "SMD_PAD_1.27X1.27MM") (field (name "AUTHOR") "CERN DEM JLC"))
      (libsource (lib "Eletro-mechanical") (part "Test Point"))
    )
    (comp (ref "TP11")
      (value "Test Point")
      (footprint "TPS127")
      (fields (field (name "PART NUMBER") "SMD_PAD_1.27X1.27MM") (field (name "AUTHOR") "CERN DEM JLC"))
      (libsource (lib "Eletro-mechanical") (part "Test Point"))
    )
    (comp (ref "TP12")
      (value "Test Point")
      (footprint "TPS127")
      (fields (field (name "PART NUMBER") "SMD_PAD_1.27X1.27MM") (field (name "AUTHOR") "CERN DEM JLC"))
      (libsource (lib "Eletro-mechanical") (part "Test Point"))
    )
    (comp (ref "U1")
      (value "LTM8083IY#PBF")
      (footprint "FP-BGA-49-05-08-1518-MFG")
      (description "36VIN, 1.5A BUCK-BOOST UMODULE")
      (libsource (lib "Altium Content Vault") (part "40255899e9ec637ba6ab0d58af5eb2d"))
    )
  )
  (nets
    (net (code "1") (name "/P5V5A") (class "Default")
      (node (ref "C1") (pin "2") (pinfunction "2_2") (pintype "passive"))
      (node (ref "C108") (pin "2") (pinfunction "2_2") (pintype "passive"))
      (node (ref "C23") (pin "2") (pinfunction "2_2") (pintype "passive"))
      (node (ref "C3") (pin "2") (pinfunction "2_2") (pintype "passive"))
      (node (ref "IC30") (pin "1") (pinfunction "IN_1") (pintype "input"))
      (node (ref "IC30") (pin "2") (pinfunction "IN_2") (pintype "input"))
      (node (ref "IC9") (pin "1") (pinfunction "IN_1") (pintype "input"))
      (node (ref "IC9") (pin "2") (pinfunction "IN_2") (pintype "input"))
      (node (ref "L18") (pin "2") (pinfunction "2_2") (pintype "passive"))
      (node (ref "R49") (pin "1") (pinfunction "1_1") (pintype "passive"))
    )
    (net (code "2") (name "/PGOOD") (class "Default")
      (node (ref "IC21") (pin "4") (pinfunction "PG_4") (pintype "output"))
      (node (ref "IC3") (pin "4") (pinfunction "PG_4") (pintype "output"))
      (node (ref "IC30") (pin "4") (pinfunction "PG_4") (pintype "output"))
      (node (ref "IC36") (pin "B4") (pinfunction "PGOOD2_B4") (pintype "open_collector"))
      (node (ref "IC36") (pin "D4") (pinfunction "PGOOD1_D4") (pintype "open_collector"))
      (node (ref "IC9") (pin "4") (pinfunction "PG_4") (pintype "output"))
    )
    (net (code "3") (name "/PSU_EN") (class "Default")
      (node (ref "IC21") (pin "3") (pinfunction "EN/UV_3") (pintype "input"))
      (node (ref "IC36") (pin "B2") (pinfunction "RUN2_B2") (pintype "input"))
      (node (ref "IC36") (pin "D2") (pinfunction "RUN1_D2") (pintype "input"))
      (node (ref "IC8") (pin "3") (pinfunction "EN/UV_3") (pintype "input"))
      (node (ref "U1") (pin "B6") (pinfunction "EN/UVLO_B6") (pintype "input"))
    )
    (net (code "4") (name "/VCC_OSC1") (class "Default")
      (node (ref "C4") (pin "2") (pinfunction "2_2") (pintype "passive"))
      (node (ref "C5") (pin "2") (pinfunction "2_2") (pintype "passive"))
      (node (ref "C6") (pin "2") (pinfunction "2_2") (pintype "passive"))
      (node (ref "IC9") (pin "10") (pinfunction "OUT_10") (pintype "output"))
      (node (ref "IC9") (pin "9") (pinfunction "OUTS_9") (pintype "output"))
      (node (ref "R24") (pin "1") (pinfunction "1_1") (pintype "passive"))
      (node (ref "R48") (pin "2") (pinfunction "2_2") (pintype "passive"))
    )
    (net (code "5") (name "/VCC_OSC2") (class "Default")
      (node (ref "C117") (pin "2") (pinfunction "2_2") (pintype "passive"))
      (node (ref "C121") (pin "2") (pinfunction "2_2") (pintype "passive"))
      (node (ref "C122") (pin "2") (pinfunction "2_2") (pintype "passive"))
      (node (ref "IC30") (pin "10") (pinfunction "OUT_10") (pintype "output"))
      (node (ref "IC30") (pin "9") (pinfunction "OUTS_9") (pintype "output"))
      (node (ref "R28") (pin "1") (pinfunction "1_1") (pintype "passive"))
    )
    (net (code "6") (name "GND") (class "Default")
      (node (ref "C1") (pin "1") (pinfunction "1_1") (pintype "passive"))
      (node (ref "C10") (pin "1") (pinfunction "1_1") (pintype "passive"))
      (node (ref "C100") (pin "1") (pinfunction "1_1") (pintype "passive"))
      (node (ref "C101") (pin "2") (pinfunction "2_2") (pintype "passive"))
      (node (ref "C102") (pin "2") (pinfunction "2_2") (pintype "passive"))
      (node (ref "C103") (pin "1") (pinfunction "1_1") (pintype "passive"))
      (node (ref "C104") (pin "1") (pinfunction "1_1") (pintype "passive"))
      (node (ref "C105") (pin "1") (pinfunction "1_1") (pintype "passive"))
      (node (ref "C108") (pin "1") (pinfunction "1_1") (pintype "passive"))
      (node (ref "C117") (pin "1") (pinfunction "1_1") (pintype "passive"))
      (node (ref "C121") (pin "1") (pinfunction "1_1") (pintype "passive"))
      (node (ref "C122") (pin "1") (pinfunction "1_1") (pintype "passive"))
      (node (ref "C123") (pin "2") (pinfunction "2_2") (pintype "passive"))
      (node (ref "C124") (pin "2") (pinfunction "2_2") (pintype "passive"))
      (node (ref "C125") (pin "1") (pinfunction "1_1") (pintype "passive"))
      (node (ref "C13") (pin "1") (pinfunction "1_1") (pintype "passive"))
      (node (ref "C14") (pin "1") (pinfunction "1_1") (pintype "passive"))
      (node (ref "C154") (pin "1") (pinfunction "1_1") (pintype "passive"))
      (node (ref "C16") (pin "1") (pinfunction "1_1") (pintype "passive"))
      (node (ref "C17") (pin "1") (pinfunction "1_1") (pintype "passive"))
      (node (ref "C19") (pin "1") (pinfunction "1_1") (pintype "passive"))
      (node (ref "C2") (pin "1") (pinfunction "1_1") (pintype "passive"))
      (node (ref "C21") (pin "1") (pinfunction "1_1") (pintype "passive"))
      (node (ref "C23") (pin "1") (pinfunction "1_1") (pintype "passive"))
      (node (ref "C24") (pin "1") (pinfunction "1_1") (pintype "passive"))
      (node (ref "C26") (pin "2") (pinfunction "2_2") (pintype "passive"))
      (node (ref "C27") (pin "1") (pinfunction "1_1") (pintype "passive"))
      (node (ref "C28") (pin "1") (pinfunction "1_1") (pintype "passive"))
      (node (ref "C3") (pin "1") (pinfunction "1_1") (pintype "passive"))
      (node (ref "C30") (pin "1") (pinfunction "1_1") (pintype "passive"))
      (node (ref "C31") (pin "1") (pinfunction "1_1") (pintype "passive"))
      (node (ref "C32") (pin "2") (pinfunction "2_2") (pintype "passive"))
      (node (ref "C4") (pin "1") (pinfunction "1_1") (pintype "passive"))
      (node (ref "C5") (pin "1") (pinfunction "1_1") (pintype "passive"))
      (node (ref "C6") (pin "1") (pinfunction "1_1") (pintype "passive"))
      (node (ref "C60") (pin "2") (pinfunction "2_2") (pintype "passive"))
      (node (ref "C65") (pin "1") (pinfunction "1_1") (pintype "passive"))
      (node (ref "C7") (pin "1") (pinfunction "1_1") (pintype "passive"))
      (node (ref "C72") (pin "1") (pinfunction "1_1") (pintype "passive"))
      (node (ref "C73") (pin "1") (pinfunction "1_1") (pintype "passive"))
      (node (ref "C74") (pin "1") (pinfunction "1_1") (pintype "passive"))
      (node (ref "C75") (pin "2") (pinfunction "2_2") (pintype "passive"))
      (node (ref "C76") (pin "1") (pinfunction "1_1") (pintype "passive"))
      (node (ref "C77") (pin "2") (pinfunction "2_2") (pintype "passive"))
      (node (ref "C8") (pin "1") (pinfunction "1_1") (pintype "passive"))
      (node (ref "C83") (pin "1") (pinfunction "1_1") (pintype "passive"))
      (node (ref "C85") (pin "2") (pinfunction "2_2") (pintype "passive"))
      (node (ref "C90") (pin "1") (pinfunction "1_1") (pintype "passive"))
      (node (ref "C91") (pin "2") (pinfunction "2_2") (pintype "passive"))
      (node (ref "C92") (pin "1") (pinfunction "1_1") (pintype "passive"))
      (node (ref "C93") (pin "2") (pinfunction "2_2") (pintype "passive"))
      (node (ref "C96") (pin "1") (pinfunction "1_1") (pintype "passive"))
      (node (ref "C98") (pin "2") (pinfunction "2_2") (pintype "passive"))
      (node (ref "D11") (pin "2") (pinfunction "A_2") (pintype "passive"))
      (node (ref "FL1") (pin "4") (pinfunction "CG_4") (pintype "passive"))
      (node (ref "IC15") (pin "2") (pinfunction "GND_2") (pintype "power_in"))
      (node (ref "IC2") (pin "2") (pinfunction "GND_2") (pintype "power_in"))
      (node (ref "IC21") (pin "11") (pinfunction "GND_11") (pintype "power_in"))
      (node (ref "IC21") (pin "5") (pinfunction "ILIM_5") (pintype "input"))
      (node (ref "IC21") (pin "8") (pinfunction "GND_8") (pintype "power_in"))
      (node (ref "IC3") (pin "11") (pinfunction "GND_11") (pintype "power_in"))
      (node (ref "IC3") (pin "5") (pinfunction "ILIM_5") (pintype "input"))
      (node (ref "IC3") (pin "8") (pinfunction "GND_8") (pintype "power_in"))
      (node (ref "IC30") (pin "11") (pinfunction "GND_11") (pintype "power_in"))
      (node (ref "IC30") (pin "5") (pinfunction "ILIM_5") (pintype "input"))
      (node (ref "IC30") (pin "8") (pinfunction "GND_8") (pintype "power_in"))
      (node (ref "IC36") (pin "B5") (pinfunction "GND_B5") (pintype "power_in"))
      (node (ref "IC36") (pin "C1") (pinfunction "GND_C1") (pintype "power_in"))
      (node (ref "IC36") (pin "C2") (pinfunction "GND_C2") (pintype "power_in"))
      (node (ref "IC36") (pin "C5") (pinfunction "SYNC/MODE_C5") (pintype "input"))
      (node (ref "IC36") (pin "D5") (pinfunction "GND_D5") (pintype "power_in"))
      (node (ref "IC8") (pin "11") (pinfunction "GND_11") (pintype "power_in"))
      (node (ref "IC8") (pin "5") (pinfunction "ILIM_5") (pintype "input"))
      (node (ref "IC8") (pin "8") (pinfunction "GND_8") (pintype "power_in"))
      (node (ref "IC9") (pin "11") (pinfunction "GND_11") (pintype "power_in"))
      (node (ref "IC9") (pin "5") (pinfunction "ILIM_5") (pintype "input"))
      (node (ref "IC9") (pin "8") (pinfunction "GND_8") (pintype "power_in"))
      (node (ref "LD1") (pin "1") (pinfunction "C_1") (pintype "passive"))
      (node (ref "LD10") (pin "1") (pinfunction "C_1") (pintype "passive"))
      (node (ref "LD11") (pin "1") (pinfunction "C_1") (pintype "passive"))
      (node (ref "LD2") (pin "1") (pinfunction "C_1") (pintype "passive"))
      (node (ref "LD3") (pin "1") (pinfunction "C_1") (pintype "passive"))
      (node (ref "LD4") (pin "1") (pinfunction "C_1") (pintype "passive"))
      (node (ref "LD8") (pin "1") (pinfunction "C_1") (pintype "passive"))
      (node (ref "R100") (pin "2") (pinfunction "2_2") (pintype "passive"))
      (node (ref "R11") (pin "1") (pinfunction "1_1") (pintype "passive"))
      (node (ref "R116") (pin "1") (pinfunction "1_1") (pintype "passive"))
      (node (ref "R142") (pin "1") (pinfunction "1_1") (pintype "passive"))
      (node (ref "R21") (pin "1") (pinfunction "1_1") (pintype "passive"))
      (node (ref "R26") (pin "1") (pinfunction "1_1") (pintype "passive"))
      (node (ref "R30") (pin "1") (pinfunction "1_1") (pintype "passive"))
      (node (ref "R32") (pin "1") (pinfunction "1_1") (pintype "passive"))
      (node (ref "R39") (pin "2") (pinfunction "2_2") (pintype "passive"))
      (node (ref "R41") (pin "2") (pinfunction "2_2") (pintype "passive"))
      (node (ref "R42") (pin "1") (pinfunction "1_1") (pintype "passive"))
      (node (ref "R47") (pin "1") (pinfunction "1_1") (pintype "passive"))
      (node (ref "R51") (pin "1") (pinfunction "1_1") (pintype "passive"))
      (node (ref "TP3") (pin "1") (pinfunction "1_1") (pintype "bidirectional"))
      (node (ref "TP4") (pin "1") (pinfunction "1_1") (pintype "bidirectional"))
      (node (ref "U1") (pin "A1") (pinfunction "GND_A1") (pintype "power_in"))
      (node (ref "U1") (pin "A2") (pinfunction "GND_A2") (pintype "power_in"))
      (node (ref "U1") (pin "A3") (pinfunction "GND_A3") (pintype "power_in"))
      (node (ref "U1") (pin "A7") (pinfunction "TST2_A7") (pintype "passive"))
      (node (ref "U1") (pin "B1") (pinfunction "GND_B1") (pintype "power_in"))
      (node (ref "U1") (pin "B2") (pinfunction "GND_B2") (pintype "power_in"))
      (node (ref "U1") (pin "B3") (pinfunction "GND_B3") (pintype "power_in"))
      (node (ref "U1") (pin "B7") (pinfunction "OVLO_B7") (pintype "input"))
      (node (ref "U1") (pin "C1") (pinfunction "GND_C1") (pintype "power_in"))
      (node (ref "U1") (pin "C2") (pinfunction "GND_C2") (pintype "power_in"))
      (node (ref "U1") (pin "C3") (pinfunction "GND_C3") (pintype "power_in"))
      (node (ref "U1") (pin "C4") (pinfunction "GND_C4") (pintype "power_in"))
      (node (ref "U1") (pin "C5") (pinfunction "GND_C5") (pintype "power_in"))
      (node (ref "U1") (pin "D1") (pinfunction "GND_D1") (pintype "power_in"))
      (node (ref "U1") (pin "D2") (pinfunction "GND_D2") (pintype "power_in"))
      (node (ref "U1") (pin "D3") (pinfunction "GND_D3") (pintype "power_in"))
      (node (ref "U1") (pin "D4") (pinfunction "GND_D4") (pintype "power_in"))
      (node (ref "U1") (pin "D5") (pinfunction "GND_D5") (pintype "power_in"))
      (node (ref "U1") (pin "D7") (pinfunction "GND_D7") (pintype "power_in"))
      (node (ref "U1") (pin "E1") (pinfunction "GND_E1") (pintype "power_in"))
      (node (ref "U1") (pin "E2") (pinfunction "GND_E2") (pintype "power_in"))
      (node (ref "U1") (pin "E3") (pinfunction "GND_E3") (pintype "power_in"))
      (node (ref "U1") (pin "E4") (pinfunction "GND_E4") (pintype "power_in"))
      (node (ref "U1") (pin "E5") (pinfunction "GND_E5") (pintype "power_in"))
      (node (ref "U1") (pin "F1") (pinfunction "GND_F1") (pintype "power_in"))
      (node (ref "U1") (pin "F2") (pinfunction "GND_F2") (pintype "power_in"))
      (node (ref "U1") (pin "G1") (pinfunction "GND_G1") (pintype "power_in"))
      (node (ref "U1") (pin "G2") (pinfunction "GND_G2") (pintype "power_in"))
      (node (ref "U1") (pin "G6") (pinfunction "SYNC_G6") (pintype "input"))
    )
    (net (code "7") (name "GNDF") (class "Default")
      (node (ref "CON1") (pin "1") (pinfunction "1_1") (pintype "bidirectional"))
      (node (ref "CON1") (pin "2") (pinfunction "2_2") (pintype "bidirectional"))
      (node (ref "FL1") (pin "3") (pinfunction "PSG_3") (pintype "passive"))
      (node (ref "J10") (pin "1") (pinfunction "1_1") (pintype "bidirectional"))
    )
    (net (code "8") (name "Net-(C19-Pad2)") (class "Default")
      (node (ref "C19") (pin "2") (pinfunction "2_2") (pintype "passive"))
      (node (ref "C75") (pin "1") (pinfunction "1_1") (pintype "passive"))
      (node (ref "IC36") (pin "A2") (pinfunction "VIN1_A2") (pintype "power_in"))
      (node (ref "IC36") (pin "B3") (pinfunction "VIN1_B3") (pintype "power_in"))
      (node (ref "IC36") (pin "D3") (pinfunction "VIN2_D3") (pintype "power_in"))
      (node (ref "IC36") (pin "E2") (pinfunction "VIN2_E2") (pintype "power_in"))
      (node (ref "L12") (pin "2") (pinfunction "2_2") (pintype "passive"))
    )
    (net (code "9") (name "Net-(C26-Pad1)") (class "Default")
      (node (ref "C26") (pin "1") (pinfunction "1_1") (pintype "passive"))
      (node (ref "C27") (pin "2") (pinfunction "2_2") (pintype "passive"))
      (node (ref "IC8") (pin "1") (pinfunction "IN_1") (pintype "input"))
      (node (ref "IC8") (pin "2") (pinfunction "IN_2") (pintype "input"))
      (node (ref "L8") (pin "2") (pinfunction "2_2") (pintype "passive"))
    )
    (net (code "10") (name "Net-(C65-Pad2)") (class "Default")
      (node (ref "C65") (pin "2") (pinfunction "2_2") (pintype "passive"))
      (node (ref "C77") (pin "1") (pinfunction "1_1") (pintype "passive"))
      (node (ref "L4") (pin "2") (pinfunction "2_2") (pintype "passive"))
      (node (ref "L6") (pin "1") (pinfunction "1_1") (pintype "passive"))
      (node (ref "L8") (pin "1") (pinfunction "1_1") (pintype "passive"))
    )
    (net (code "11") (name "Net-(C85-Pad1)") (class "Default")
      (node (ref "C85") (pin "1") (pinfunction "1_1") (pintype "passive"))
      (node (ref "C92") (pin "2") (pinfunction "2_2") (pintype "passive"))
      (node (ref "IC21") (pin "1") (pinfunction "IN_1") (pintype "input"))
      (node (ref "IC21") (pin "2") (pinfunction "IN_2") (pintype "input"))
      (node (ref "L6") (pin "2") (pinfunction "2_2") (pintype "passive"))
    )
    (net (code "12") (name "Net-(IC3-EN{slash}UV)") (class "Default")
      (node (ref "C102") (pin "1") (pinfunction "1_1") (pintype "passive"))
      (node (ref "C2") (pin "2") (pinfunction "2_2") (pintype "passive"))
      (node (ref "IC3") (pin "1") (pinfunction "IN_1") (pintype "input"))
      (node (ref "IC3") (pin "2") (pinfunction "IN_2") (pintype "input"))
      (node (ref "IC3") (pin "3") (pinfunction "EN/UV_3") (pintype "input"))
      (node (ref "L1") (pin "2") (pinfunction "2_2") (pintype "passive"))
    )
    (net (code "13") (name "Net-(IC3-PGFB)") (class "Default")
      (node (ref "IC3") (pin "6") (pinfunction "PGFB_6") (pintype "input"))
      (node (ref "R32") (pin "2") (pinfunction "2_2") (pintype "passive"))
      (node (ref "R33") (pin "1") (pinfunction "1_1") (pintype "passive"))
    )
    (net (code "14") (name "Net-(IC3-SET)") (class "Default")
      (node (ref "C101") (pin "1") (pinfunction "1_1") (pintype "passive"))
      (node (ref "IC3") (pin "7") (pinfunction "SET_7") (pintype "input"))
      (node (ref "R39") (pin "1") (pinfunction "1_1") (pintype "passive"))
    )
    (net (code "15") (name "Net-(IC8-PGFB)") (class "Default")
      (node (ref "IC8") (pin "6") (pinfunction "PGFB_6") (pintype "input"))
      (node (ref "R42") (pin "2") (pinfunction "2_2") (pintype "passive"))
      (node (ref "R43") (pin "1") (pinfunction "1_1") (pintype "passive"))
    )
    (net (code "16") (name "Net-(IC8-SET)") (class "Default")
      (node (ref "C32") (pin "1") (pinfunction "1_1") (pintype "passive"))
      (node (ref "IC8") (pin "7") (pinfunction "SET_7") (pintype "input"))
      (node (ref "R40") (pin "1") (pinfunction "1_1") (pintype "passive"))
    )
    (net (code "17") (name "Net-(IC21-PGFB)") (class "Default")
      (node (ref "IC21") (pin "6") (pinfunction "PGFB_6") (pintype "input"))
      (node (ref "R100") (pin "1") (pinfunction "1_1") (pintype "passive"))
      (node (ref "R135") (pin "2") (pinfunction "2_2") (pintype "passive"))
    )
    (net (code "18") (name "Net-(IC21-SET)") (class "Default")
      (node (ref "C91") (pin "1") (pinfunction "1_1") (pintype "passive"))
      (node (ref "IC21") (pin "7") (pinfunction "SET_7") (pintype "input"))
      (node (ref "R117") (pin "2") (pinfunction "2_2") (pintype "passive"))
    )
    (net (code "19") (name "Net-(IC30-EN{slash}UV)") (class "Default")
      (node (ref "IC30") (pin "3") (pinfunction "EN/UV_3") (pintype "input"))
      (node (ref "IC9") (pin "3") (pinfunction "EN/UV_3") (pintype "input"))
      (node (ref "R49") (pin "2") (pinfunction "2_2") (pintype "passive"))
    )
    (net (code "20") (name "Net-(IC30-PGFB)") (class "Default")
      (node (ref "IC30") (pin "6") (pinfunction "PGFB_6") (pintype "input"))
      (node (ref "IC9") (pin "6") (pinfunction "PGFB_6") (pintype "input"))
      (node (ref "R47") (pin "2") (pinfunction "2_2") (pintype "passive"))
      (node (ref "R48") (pin "1") (pinfunction "1_1") (pintype "passive"))
    )
    (net (code "21") (name "Net-(IC30-SET)") (class "Default")
      (node (ref "C123") (pin "1") (pinfunction "1_1") (pintype "passive"))
      (node (ref "C93") (pin "1") (pinfunction "1_1") (pintype "passive"))
      (node (ref "IC30") (pin "7") (pinfunction "SET_7") (pintype "input"))
      (node (ref "IC9") (pin "7") (pinfunction "SET_7") (pintype "input"))
      (node (ref "R116") (pin "2") (pinfunction "2_2") (pintype "passive"))
      (node (ref "R51") (pin "2") (pinfunction "2_2") (pintype "passive"))
    )
    (net (code "22") (name "Net-(IC36-FB1)") (class "Default")
      (node (ref "IC36") (pin "E4") (pinfunction "FB1_E4") (pintype "input"))
      (node (ref "R9") (pin "2") (pinfunction "2_2") (pintype "passive"))
    )
    (net (code "23") (name "Net-(IC36-FB2)") (class "Default")
      (node (ref "IC36") (pin "A4") (pinfunction "FB2_A4") (pintype "input"))
      (node (ref "R20") (pin "2") (pinfunction "2_2") (pintype "passive"))
    )
    (net (code "24") (name "Net-(IC36-TRACK{slash}SS1)") (class "Default")
      (node (ref "C154") (pin "2") (pinfunction "2_2") (pintype "passive"))
      (node (ref "IC36") (pin "E3") (pinfunction "TRACK/SS1_E3") (pintype "input"))
    )
    (net (code "25") (name "Net-(IC36-TRACK{slash}SS2)") (class "Default")
      (node (ref "C76") (pin "2") (pinfunction "2_2") (pintype "passive"))
      (node (ref "IC36") (pin "A3") (pinfunction "TRACK/SS2_A3") (pintype "input"))
    )
    (net (code "26") (name "Net-(L1-Pad1)") (class "Default")
      (node (ref "L1") (pin "1") (pinfunction "1_1") (pintype "passive"))
      (node (ref "L2") (pin "2") (pinfunction "2_2") (pintype "passive"))
    )
    (net (code "27") (name "Net-(L17-Pad1)") (class "Default")
      (node (ref "L17") (pin "1") (pinfunction "1_1") (pintype "passive"))
      (node (ref "R167") (pin "2") (pinfunction "2_2") (pintype "passive"))
      (node (ref "R72") (pin "2") (pinfunction "2_2") (pintype "passive"))
    )
    (net (code "28") (name "Net-(L17-Pad2)") (class "Default")
      (node (ref "L17") (pin "2") (pinfunction "2_2") (pintype "passive"))
      (node (ref "L18") (pin "1") (pinfunction "1_1") (pintype "passive"))
    )
    (net (code "29") (name "Net-(LD1-A)") (class "Default")
      (node (ref "LD1") (pin "2") (pinfunction "A_2") (pintype "passive"))
      (node (ref "R4") (pin "1") (pinfunction "1_1") (pintype "passive"))
    )
    (net (code "30") (name "Net-(LD2-A)") (class "Default")
      (node (ref "LD2") (pin "2") (pinfunction "A_2") (pintype "passive"))
      (node (ref "R5") (pin "1") (pinfunction "1_1") (pintype "passive"))
    )
    (net (code "31") (name "Net-(LD3-A)") (class "Default")
      (node (ref "LD3") (pin "2") (pinfunction "A_2") (pintype "passive"))
      (node (ref "R6") (pin "1") (pinfunction "1_1") (pintype "passive"))
    )
    (net (code "32") (name "Net-(LD4-A)") (class "Default")
      (node (ref "LD4") (pin "2") (pinfunction "A_2") (pintype "passive"))
      (node (ref "R7") (pin "1") (pinfunction "1_1") (pintype "passive"))
    )
    (net (code "33") (name "Net-(LD8-A)") (class "Default")
      (node (ref "LD8") (pin "2") (pinfunction "A_2") (pintype "passive"))
      (node (ref "R65") (pin "1") (pinfunction "1_1") (pintype "passive"))
    )
    (net (code "34") (name "Net-(LD10-A)") (class "Default")
      (node (ref "LD10") (pin "2") (pinfunction "A_2") (pintype "passive"))
      (node (ref "R131") (pin "1") (pinfunction "1_1") (pintype "passive"))
    )
    (net (code "35") (name "Net-(LD11-A)") (class "Default")
      (node (ref "LD11") (pin "2") (pinfunction "A_2") (pintype "passive"))
      (node (ref "R1") (pin "1") (pinfunction "1_1") (pintype "passive"))
    )
    (net (code "36") (name "Net-(R20-Pad1)") (class "Default")
      (node (ref "R20") (pin "1") (pinfunction "1_1") (pintype "passive"))
      (node (ref "R26") (pin "2") (pinfunction "2_2") (pintype "passive"))
    )
    (net (code "37") (name "Net-(R21-Pad2)") (class "Default")
      (node (ref "R21") (pin "2") (pinfunction "2_2") (pintype "passive"))
      (node (ref "R9") (pin "1") (pinfunction "1_1") (pintype "passive"))
    )
    (net (code "38") (name "Net-(R40-Pad2)") (class "Default")
      (node (ref "R40") (pin "2") (pinfunction "2_2") (pintype "passive"))
      (node (ref "R41") (pin "1") (pinfunction "1_1") (pintype "passive"))
    )
    (net (code "39") (name "Net-(R117-Pad1)") (class "Default")
      (node (ref "R117") (pin "1") (pinfunction "1_1") (pintype "passive"))
      (node (ref "R142") (pin "2") (pinfunction "2_2") (pintype "passive"))
    )
    (net (code "40") (name "Net-(U1A-FB)") (class "Default")
      (node (ref "R30") (pin "2") (pinfunction "2_2") (pintype "passive"))
      (node (ref "R8") (pin "1") (pinfunction "1_1") (pintype "passive"))
      (node (ref "U1") (pin "F7") (pinfunction "FB_F7") (pintype "input"))
    )
    (net (code "41") (name "Net-(U1A-ISN)") (class "Default")
      (node (ref "C72") (pin "2") (pinfunction "2_2") (pintype "passive"))
      (node (ref "L10") (pin "1") (pinfunction "1_1") (pintype "passive"))
      (node (ref "R8") (pin "2") (pinfunction "2_2") (pintype "passive"))
      (node (ref "U1") (pin "F3") (pinfunction "ISN_F3") (pintype "passive"))
      (node (ref "U1") (pin "F4") (pinfunction "VOUT_F4") (pintype "passive"))
      (node (ref "U1") (pin "F5") (pinfunction "VOUT_F5") (pintype "passive"))
      (node (ref "U1") (pin "G3") (pinfunction "ISP_G3") (pintype "passive"))
      (node (ref "U1") (pin "G4") (pinfunction "VOUT_G4") (pintype "passive"))
      (node (ref "U1") (pin "G5") (pinfunction "VOUT_G5") (pintype "passive"))
    )
    (net (code "42") (name "Net-(U1A-RT)") (class "Default")
      (node (ref "R11") (pin "2") (pinfunction "2_2") (pintype "passive"))
      (node (ref "U1") (pin "E7") (pinfunction "RT_E7") (pintype "input"))
    )
    (net (code "43") (name "Net-(U1A-SS)") (class "Default")
      (node (ref "C24") (pin "2") (pinfunction "2_2") (pintype "passive"))
      (node (ref "U1") (pin "F6") (pinfunction "SS_F6") (pintype "input"))
    )
    (net (code "44") (name "Net-(U1A-SVIN)") (class "Default")
      (node (ref "C105") (pin "2") (pinfunction "2_2") (pintype "passive"))
      (node (ref "C60") (pin "1") (pinfunction "1_1") (pintype "passive"))
      (node (ref "L3") (pin "2") (pinfunction "2_2") (pintype "passive"))
      (node (ref "U1") (pin "A4") (pinfunction "VIN_A4") (pintype "power_in"))
      (node (ref "U1") (pin "A5") (pinfunction "VIN_A5") (pintype "power_in"))
      (node (ref "U1") (pin "A6") (pinfunction "SVIN_A6") (pintype "power_in"))
      (node (ref "U1") (pin "B4") (pinfunction "VIN_B4") (pintype "power_in"))
      (node (ref "U1") (pin "B5") (pinfunction "VIN_B5") (pintype "power_in"))
    )
    (net (code "45") (name "P3V3") (class "Default")
      (node (ref "C103") (pin "2") (pinfunction "2_2") (pintype "passive"))
      (node (ref "C104") (pin "2") (pinfunction "2_2") (pintype "passive"))
      (node (ref "D7") (pin "2") (pinfunction "A_2") (pintype "passive"))
      (node (ref "IC15") (pin "5") (pinfunction "OUT_5") (pintype "power_in"))
      (node (ref "R65") (pin "2") (pinfunction "2_2") (pintype "passive"))
      (node (ref "TP12") (pin "1") (pinfunction "1_1") (pintype "bidirectional"))
    )
    (net (code "46") (name "P3V3A") (class "Default")
      (node (ref "C14") (pin "2") (pinfunction "2_2") (pintype "passive"))
      (node (ref "C16") (pin "2") (pinfunction "2_2") (pintype "passive"))
      (node (ref "C17") (pin "2") (pinfunction "2_2") (pintype "passive"))
      (node (ref "IC3") (pin "10") (pinfunction "OUT_10") (pintype "output"))
      (node (ref "IC3") (pin "9") (pinfunction "OUTS_9") (pintype "output"))
      (node (ref "R1") (pin "2") (pinfunction "2_2") (pintype "passive"))
      (node (ref "R33") (pin "2") (pinfunction "2_2") (pintype "passive"))
      (node (ref "TP2") (pin "1") (pinfunction "1_1") (pintype "bidirectional"))
    )
    (net (code "47") (name "P3V3_CPCIS") (class "Default")
      (node (ref "C10") (pin "2") (pinfunction "2_2") (pintype "passive"))
      (node (ref "C13") (pin "2") (pinfunction "2_2") (pintype "passive"))
      (node (ref "D1") (pin "2") (pinfunction "A_2") (pintype "passive"))
      (node (ref "IC2") (pin "5") (pinfunction "OUT_5") (pintype "power_in"))
      (node (ref "R4") (pin "2") (pinfunction "2_2") (pintype "passive"))
      (node (ref "TP11") (pin "1") (pinfunction "1_1") (pintype "bidirectional"))
    )
    (net (code "48") (name "P3V3_MP") (class "Default")
      (node (ref "D1") (pin "1") (pinfunction "C_1") (pintype "passive"))
      (node (ref "D7") (pin "1") (pinfunction "C_1") (pintype "passive"))
    )
    (net (code "49") (name "P3V6") (class "Default")
      (node (ref "C100") (pin "2") (pinfunction "2_2") (pintype "passive"))
      (node (ref "C73") (pin "2") (pinfunction "2_2") (pintype "passive"))
      (node (ref "IC15") (pin "1") (pinfunction "IN_1") (pintype "input"))
      (node (ref "IC15") (pin "3") (pinfunction "EN_3") (pintype "input"))
      (node (ref "IC36") (pin "D1") (pinfunction "VOUT1_D1") (pintype "power_in"))
      (node (ref "IC36") (pin "E1") (pinfunction "VOUT1_E1") (pintype "power_in"))
      (node (ref "L2") (pin "1") (pinfunction "1_1") (pintype "passive"))
    )
    (net (code "50") (name "P5V4A") (class "Default")
      (node (ref "C83") (pin "2") (pinfunction "2_2") (pintype "passive"))
      (node (ref "C90") (pin "2") (pinfunction "2_2") (pintype "passive"))
      (node (ref "C96") (pin "2") (pinfunction "2_2") (pintype "passive"))
      (node (ref "IC21") (pin "10") (pinfunction "OUT_10") (pintype "output"))
      (node (ref "IC21") (pin "9") (pinfunction "OUTS_9") (pintype "output"))
      (node (ref "R135") (pin "1") (pinfunction "1_1") (pintype "passive"))
      (node (ref "R5") (pin "2") (pinfunction "2_2") (pintype "passive"))
      (node (ref "TP8") (pin "1") (pinfunction "1_1") (pintype "bidirectional"))
    )
    (net (code "51") (name "P5V5") (class "Default")
      (node (ref "C21") (pin "2") (pinfunction "2_2") (pintype "passive"))
      (node (ref "IC36") (pin "A1") (pinfunction "VOUT2_A1") (pintype "power_in"))
      (node (ref "IC36") (pin "B1") (pinfunction "VOUT2_B1") (pintype "power_in"))
      (node (ref "R167") (pin "1") (pinfunction "1_1") (pintype "passive"))
    )
    (net (code "52") (name "P10V5A") (class "Default")
      (node (ref "C28") (pin "2") (pinfunction "2_2") (pintype "passive"))
      (node (ref "C30") (pin "2") (pinfunction "2_2") (pintype "passive"))
      (node (ref "C31") (pin "2") (pinfunction "2_2") (pintype "passive"))
      (node (ref "IC8") (pin "10") (pinfunction "OUT_10") (pintype "output"))
      (node (ref "IC8") (pin "9") (pinfunction "OUTS_9") (pintype "output"))
      (node (ref "R43") (pin "2") (pinfunction "2_2") (pintype "passive"))
      (node (ref "R7") (pin "2") (pinfunction "2_2") (pintype "passive"))
      (node (ref "TP10") (pin "1") (pinfunction "1_1") (pintype "bidirectional"))
    )
    (net (code "53") (name "P12V0") (class "Default")
      (node (ref "C7") (pin "2") (pinfunction "2_2") (pintype "passive"))
      (node (ref "C74") (pin "2") (pinfunction "2_2") (pintype "passive"))
      (node (ref "C98") (pin "1") (pinfunction "1_1") (pintype "passive"))
      (node (ref "D11") (pin "1") (pinfunction "C_1") (pintype "passive"))
      (node (ref "FL1") (pin "2") (pinfunction "CB_2") (pintype "passive"))
      (node (ref "L12") (pin "1") (pinfunction "1_1") (pintype "passive"))
      (node (ref "L3") (pin "1") (pinfunction "1_1") (pintype "passive"))
      (node (ref "L4") (pin "1") (pinfunction "1_1") (pintype "passive"))
      (node (ref "R131") (pin "2") (pinfunction "2_2") (pintype "passive"))
      (node (ref "TP1") (pin "1") (pinfunction "1_1") (pintype "bidirectional"))
    )
    (net (code "54") (name "P12V0F") (class "Default")
      (node (ref "CON1") (pin "3") (pinfunction "3_3") (pintype "bidirectional"))
      (node (ref "CON1") (pin "4") (pinfunction "4_4") (pintype "bidirectional"))
      (node (ref "FL1") (pin "1") (pinfunction "B_1") (pintype "passive"))
      (node (ref "J10") (pin "3") (pinfunction "3_3") (pintype "bidirectional"))
    )
    (net (code "55") (name "P12V0_CPCIS") (class "Default")
      (node (ref "C8") (pin "2") (pinfunction "2_2") (pintype "passive"))
      (node (ref "IC2") (pin "1") (pinfunction "IN_1") (pintype "input"))
      (node (ref "IC2") (pin "3") (pinfunction "EN_3") (pintype "input"))
    )
    (net (code "56") (name "P13V0") (class "Default")
      (node (ref "C124") (pin "1") (pinfunction "1_1") (pintype "passive"))
      (node (ref "C125") (pin "2") (pinfunction "2_2") (pintype "passive"))
      (node (ref "L10") (pin "2") (pinfunction "2_2") (pintype "passive"))
      (node (ref "R72") (pin "1") (pinfunction "1_1") (pintype "passive"))
    )
    (net (code "57") (name "VCC_OSC") (class "Default")
      (node (ref "R24") (pin "2") (pinfunction "2_2") (pintype "passive"))
      (node (ref "R28") (pin "2") (pinfunction "2_2") (pintype "passive"))
      (node (ref "R6") (pin "2") (pinfunction "2_2") (pintype "passive"))
      (node (ref "TP9") (pin "1") (pinfunction "1_1") (pintype "bidirectional"))
    )
    (net (code "58") (name "unconnected-(IC2-BYP-Pad4)") (class "Default")
      (node (ref "IC2") (pin "4") (pinfunction "BYP_4") (pintype "passive+no_connect"))
    )
    (net (code "59") (name "unconnected-(IC8-PG-Pad4)") (class "Default")
      (node (ref "IC8") (pin "4") (pinfunction "PG_4") (pintype "output"))
    )
    (net (code "60") (name "unconnected-(IC15-BYP-Pad4)") (class "Default")
      (node (ref "IC15") (pin "4") (pinfunction "BYP_4") (pintype "passive+no_connect"))
    )
    (net (code "61") (name "unconnected-(IC36-COMP1-PadE5)") (class "Default")
      (node (ref "IC36") (pin "E5") (pinfunction "COMP1_E5") (pintype "input+no_connect"))
    )
    (net (code "62") (name "unconnected-(IC36-COMP2-PadA5)") (class "Default")
      (node (ref "IC36") (pin "A5") (pinfunction "COMP2_A5") (pintype "input+no_connect"))
    )
    (net (code "63") (name "unconnected-(IC36-FREQ-PadC4)") (class "Default")
      (node (ref "IC36") (pin "C4") (pinfunction "FREQ_C4") (pintype "input+no_connect"))
    )
    (net (code "64") (name "unconnected-(IC36-INTVCC-PadC3)") (class "Default")
      (node (ref "IC36") (pin "C3") (pinfunction "INTVCC_C3") (pintype "power_in"))
    )
    (net (code "65") (name "unconnected-(J10-Pad2)") (class "Default")
      (node (ref "J10") (pin "2") (pinfunction "2_2") (pintype "bidirectional"))
    )
    (net (code "66") (name "unconnected-(U1A-CTRL-PadC7)") (class "Default")
      (node (ref "U1") (pin "C7") (pinfunction "CTRL_C7") (pintype "passive"))
    )
    (net (code "67") (name "unconnected-(U1A-INTVCC-PadC6)") (class "Default")
      (node (ref "U1") (pin "C6") (pinfunction "INTVCC_C6") (pintype "power_in"))
    )
    (net (code "68") (name "unconnected-(U1A-ISMON-PadD6)") (class "Default")
      (node (ref "U1") (pin "D6") (pinfunction "ISMON_D6") (pintype "passive+no_connect"))
    )
    (net (code "69") (name "unconnected-(U1A-TST1-PadG7)") (class "Default")
      (node (ref "U1") (pin "G7") (pinfunction "TST1_G7") (pintype "passive"))
    )
    (net (code "70") (name "unconnected-(U1A-VC-PadE6)") (class "Default")
      (node (ref "U1") (pin "E6") (pinfunction "VC_E6") (pintype "passive+no_connect"))
    )
  )
)
